# axiom_beta_sensor_cmv12000_tht_v0_16_r1_.net
KiCad netlist of a schematic drawn in EAGLE
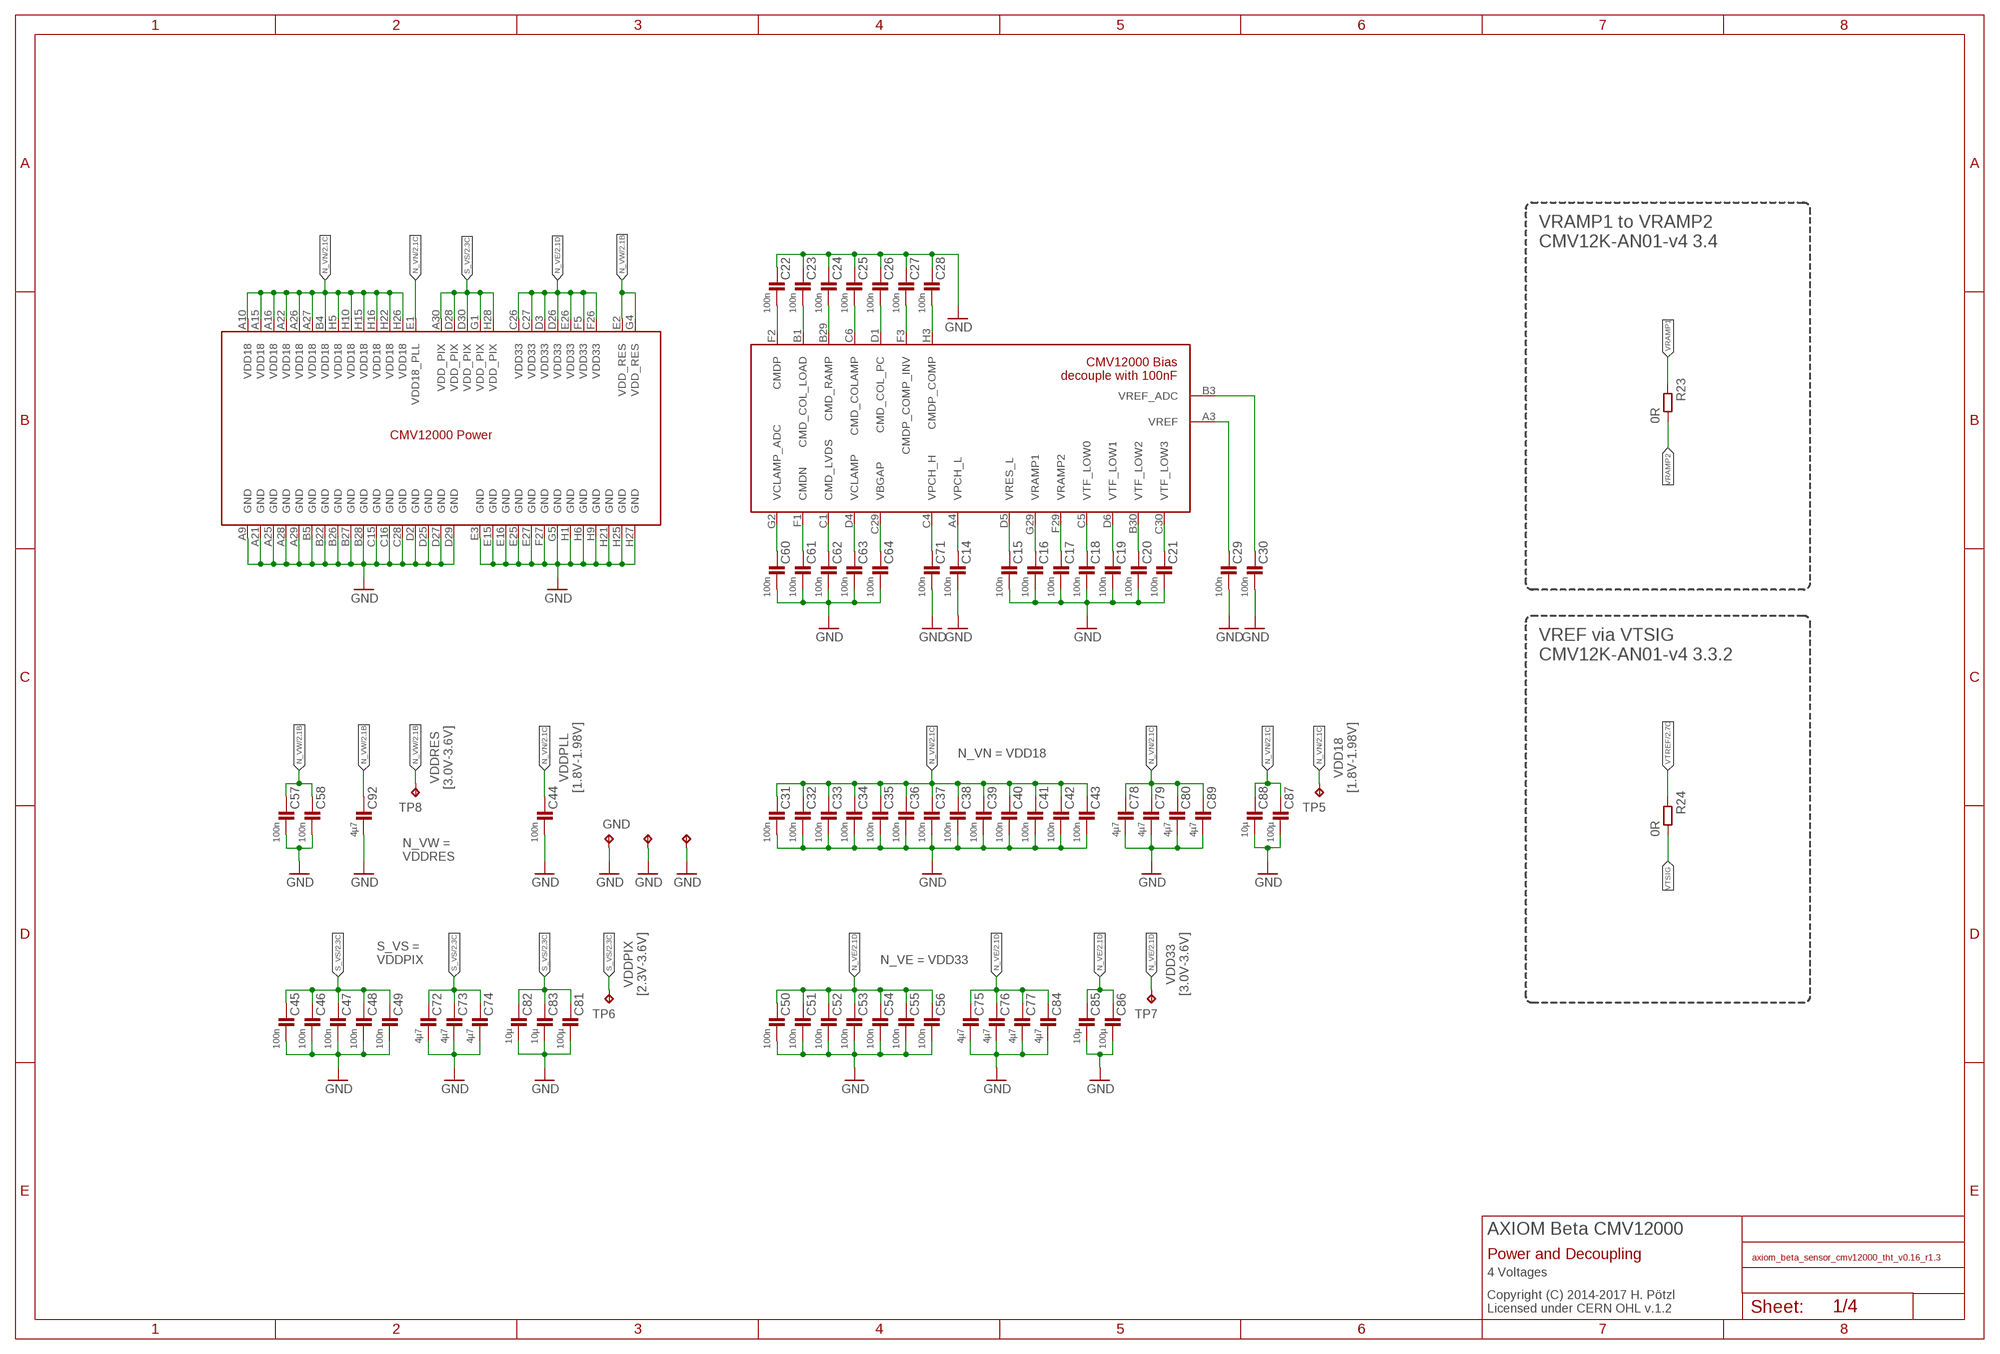
[diagram p0: schematic, sheet 1]
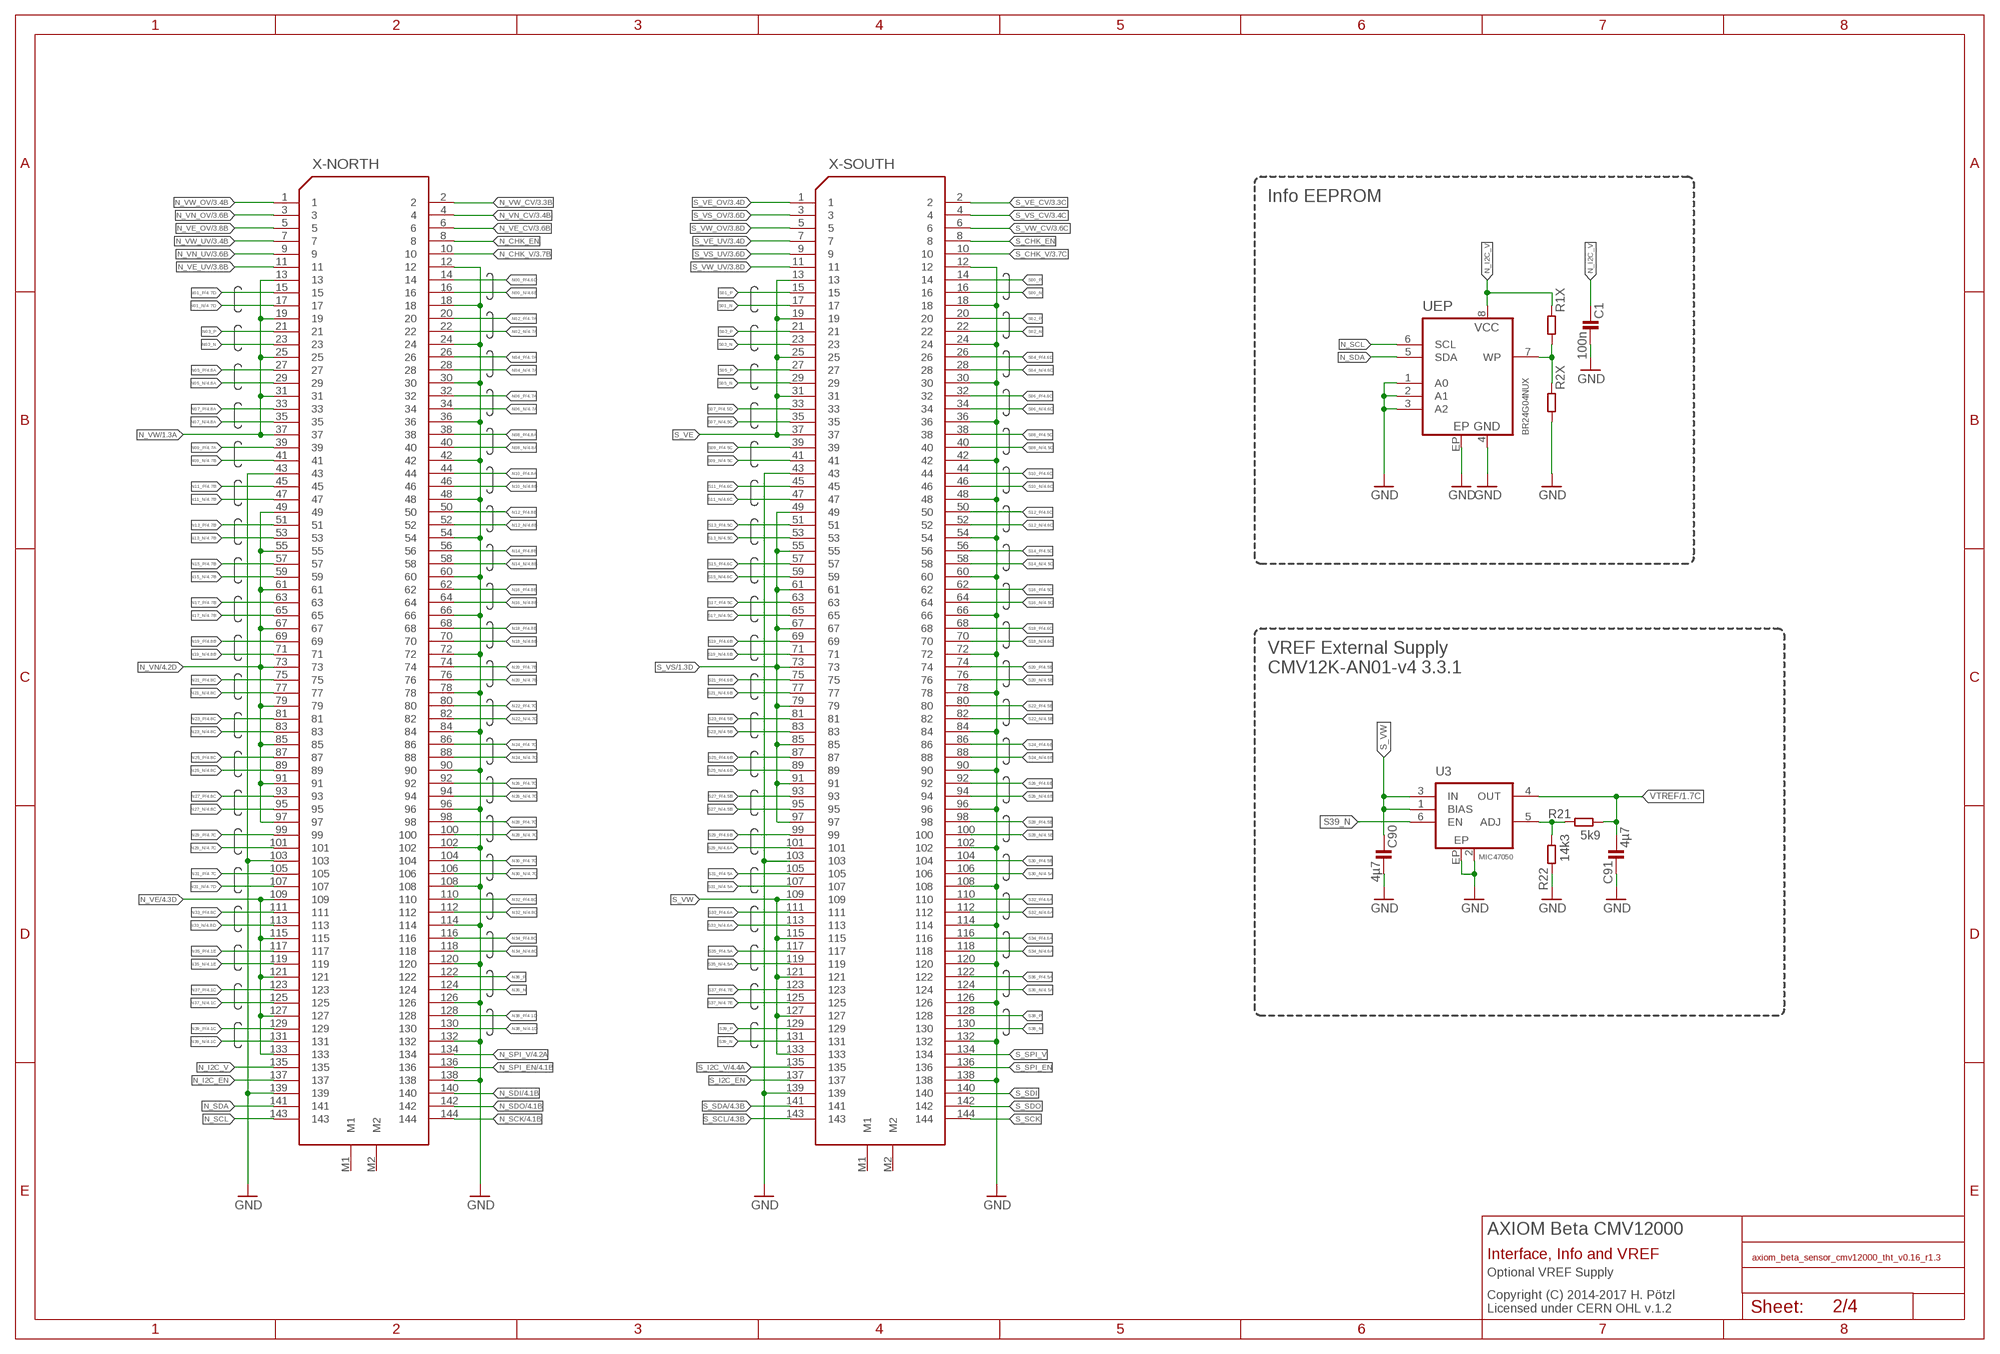
[diagram p1: schematic, sheet 2]
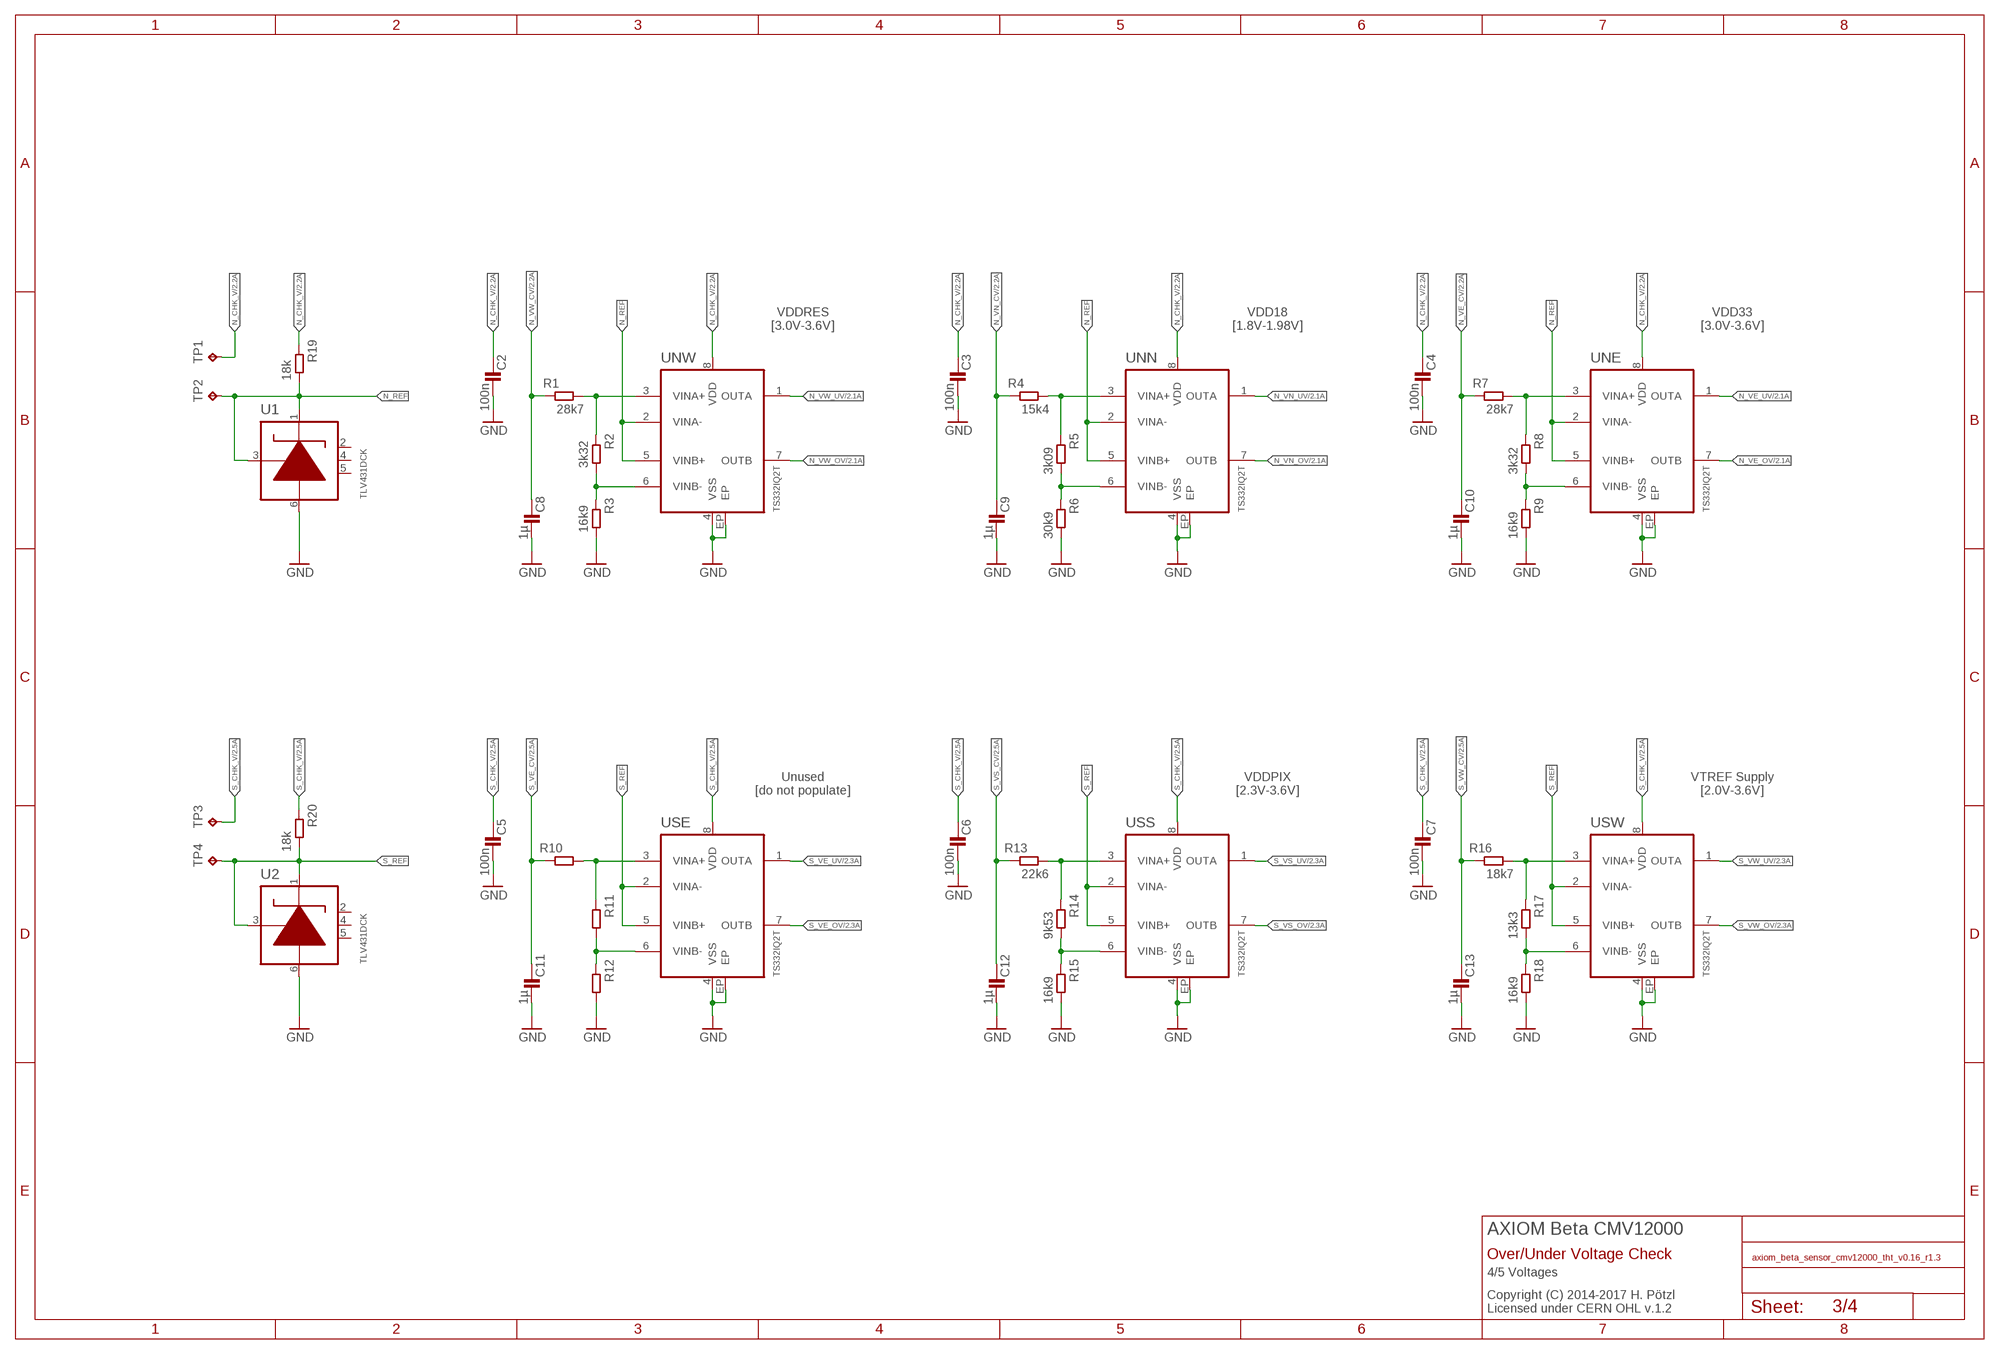
[diagram p2: schematic, sheet 3]
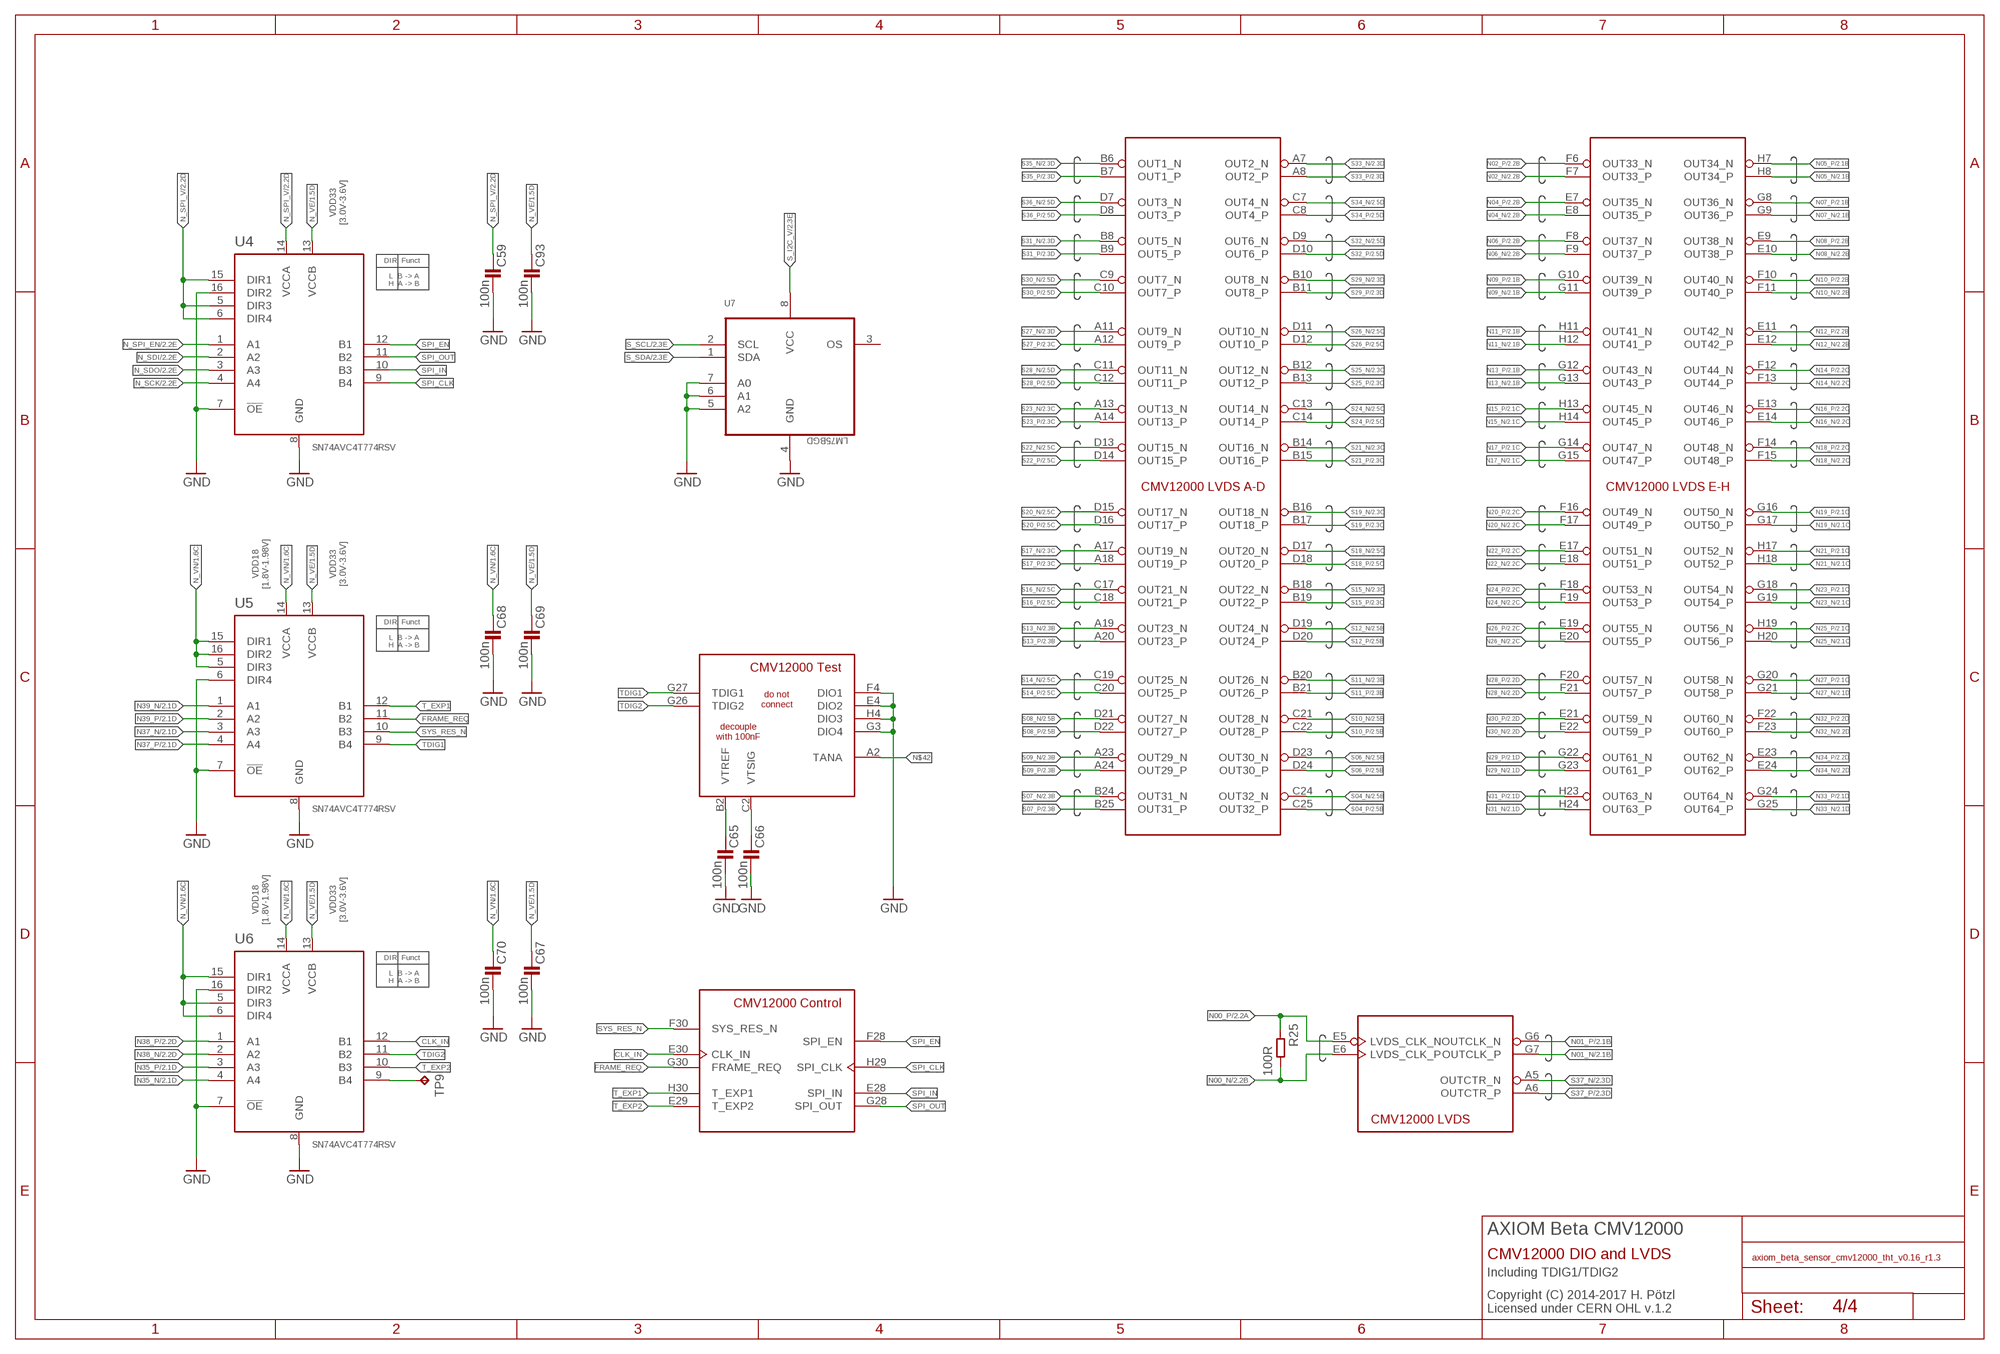
[diagram p3: schematic, sheet 4]

(export (version "E")
  (design (tool "Eeschema 10.0.6"))
  (components
    (comp (ref "C1")
      (value "100n")
      (footprint "eagle-import:0402-C")
      (libsource (lib "eagle-import") (part "C0402-C"))
    )
    (comp (ref "C90")
      (value "4µ7")
      (footprint "eagle-import:0402-C")
      (libsource (lib "eagle-import") (part "C0402-C"))
    )
    (comp (ref "C91")
      (value "4µ7")
      (footprint "eagle-import:0402-C")
      (libsource (lib "eagle-import") (part "C0402-C"))
    )
    (comp (ref "R1X")
      (value "R0402-C")
      (footprint "eagle-import:0402-C")
      (libsource (lib "eagle-import") (part "R0402-C"))
    )
    (comp (ref "R2X")
      (value "R0402-C")
      (footprint "eagle-import:0402-C")
      (libsource (lib "eagle-import") (part "R0402-C"))
    )
    (comp (ref "R21")
      (value "5k9")
      (footprint "eagle-import:0402-C")
      (libsource (lib "eagle-import") (part "R0402-C"))
    )
    (comp (ref "R22")
      (value "14k3")
      (footprint "eagle-import:0402-C")
      (libsource (lib "eagle-import") (part "R0402-C"))
    )
    (comp (ref "U3")
      (value "MIC47050")
      (footprint "eagle-import:MLF-6")
      (libsource (lib "eagle-import") (part "MIC47050-ADJ"))
    )
    (comp (ref "UEP")
      (value "BR24G04NUX")
      (footprint "eagle-import:DFN200X300X100-9N")
      (libsource (lib "eagle-import") (part "BR24G04NUX"))
    )
    (comp (ref "X-NORTH")
      (value "FX10-144P")
      (footprint "eagle-import:FX10A-144P")
      (libsource (lib "eagle-import") (part "FX10-144P"))
    )
    (comp (ref "X-SOUTH")
      (value "FX10-144P")
      (footprint "eagle-import:FX10A-144P")
      (libsource (lib "eagle-import") (part "FX10-144P"))
    )
    (comp (ref "C2")
      (value "100n")
      (footprint "eagle-import:0402-C")
      (libsource (lib "eagle-import") (part "C0402-C"))
    )
    (comp (ref "C3")
      (value "100n")
      (footprint "eagle-import:0402-C")
      (libsource (lib "eagle-import") (part "C0402-C"))
    )
    (comp (ref "C4")
      (value "100n")
      (footprint "eagle-import:0402-C")
      (libsource (lib "eagle-import") (part "C0402-C"))
    )
    (comp (ref "C5")
      (value "100n")
      (footprint "eagle-import:0402-C")
      (libsource (lib "eagle-import") (part "C0402-C"))
    )
    (comp (ref "C6")
      (value "100n")
      (footprint "eagle-import:0402-C")
      (libsource (lib "eagle-import") (part "C0402-C"))
    )
    (comp (ref "C7")
      (value "100n")
      (footprint "eagle-import:0402-C")
      (libsource (lib "eagle-import") (part "C0402-C"))
    )
    (comp (ref "C8")
      (value "1µ")
      (footprint "eagle-import:0402-C")
      (libsource (lib "eagle-import") (part "C0402-C"))
    )
    (comp (ref "C9")
      (value "1µ")
      (footprint "eagle-import:0402-C")
      (libsource (lib "eagle-import") (part "C0402-C"))
    )
    (comp (ref "C10")
      (value "1µ")
      (footprint "eagle-import:0402-C")
      (libsource (lib "eagle-import") (part "C0402-C"))
    )
    (comp (ref "C11")
      (value "1µ")
      (footprint "eagle-import:0402-C")
      (libsource (lib "eagle-import") (part "C0402-C"))
    )
    (comp (ref "C12")
      (value "1µ")
      (footprint "eagle-import:0402-C")
      (libsource (lib "eagle-import") (part "C0402-C"))
    )
    (comp (ref "C13")
      (value "1µ")
      (footprint "eagle-import:0402-C")
      (libsource (lib "eagle-import") (part "C0402-C"))
    )
    (comp (ref "R1")
      (value "28k7")
      (footprint "eagle-import:0402-C")
      (libsource (lib "eagle-import") (part "R0402-C"))
    )
    (comp (ref "R2")
      (value "3k32")
      (footprint "eagle-import:0402-C")
      (libsource (lib "eagle-import") (part "R0402-C"))
    )
    (comp (ref "R3")
      (value "16k9")
      (footprint "eagle-import:0402-C")
      (libsource (lib "eagle-import") (part "R0402-C"))
    )
    (comp (ref "R4")
      (value "15k4")
      (footprint "eagle-import:0402-C")
      (libsource (lib "eagle-import") (part "R0402-C"))
    )
    (comp (ref "R5")
      (value "3k09")
      (footprint "eagle-import:0402-C")
      (libsource (lib "eagle-import") (part "R0402-C"))
    )
    (comp (ref "R6")
      (value "30k9")
      (footprint "eagle-import:0402-C")
      (libsource (lib "eagle-import") (part "R0402-C"))
    )
    (comp (ref "R7")
      (value "28k7")
      (footprint "eagle-import:0402-C")
      (libsource (lib "eagle-import") (part "R0402-C"))
    )
    (comp (ref "R8")
      (value "3k32")
      (footprint "eagle-import:0402-C")
      (libsource (lib "eagle-import") (part "R0402-C"))
    )
    (comp (ref "R9")
      (value "16k9")
      (footprint "eagle-import:0402-C")
      (libsource (lib "eagle-import") (part "R0402-C"))
    )
    (comp (ref "R10")
      (value "R0402-C")
      (footprint "eagle-import:0402-C")
      (libsource (lib "eagle-import") (part "R0402-C"))
    )
    (comp (ref "R11")
      (value "R0402-C")
      (footprint "eagle-import:0402-C")
      (libsource (lib "eagle-import") (part "R0402-C"))
    )
    (comp (ref "R12")
      (value "R0402-C")
      (footprint "eagle-import:0402-C")
      (libsource (lib "eagle-import") (part "R0402-C"))
    )
    (comp (ref "R13")
      (value "22k6")
      (footprint "eagle-import:0402-C")
      (libsource (lib "eagle-import") (part "R0402-C"))
    )
    (comp (ref "R14")
      (value "9k53")
      (footprint "eagle-import:0402-C")
      (libsource (lib "eagle-import") (part "R0402-C"))
    )
    (comp (ref "R15")
      (value "16k9")
      (footprint "eagle-import:0402-C")
      (libsource (lib "eagle-import") (part "R0402-C"))
    )
    (comp (ref "R16")
      (value "18k7")
      (footprint "eagle-import:0402-C")
      (libsource (lib "eagle-import") (part "R0402-C"))
    )
    (comp (ref "R17")
      (value "13k3")
      (footprint "eagle-import:0402-C")
      (libsource (lib "eagle-import") (part "R0402-C"))
    )
    (comp (ref "R18")
      (value "16k9")
      (footprint "eagle-import:0402-C")
      (libsource (lib "eagle-import") (part "R0402-C"))
    )
    (comp (ref "R19")
      (value "18k")
      (footprint "eagle-import:0402-C")
      (libsource (lib "eagle-import") (part "R0402-C"))
    )
    (comp (ref "R20")
      (value "18k")
      (footprint "eagle-import:0402-C")
      (libsource (lib "eagle-import") (part "R0402-C"))
    )
    (comp (ref "TP1")
      (value "TPTP10R")
      (footprint "eagle-import:TP10R")
      (libsource (lib "eagle-import") (part "TPTP10R"))
    )
    (comp (ref "TP2")
      (value "TPTP10R")
      (footprint "eagle-import:TP10R")
      (libsource (lib "eagle-import") (part "TPTP10R"))
    )
    (comp (ref "TP3")
      (value "TPTP10R")
      (footprint "eagle-import:TP10R")
      (libsource (lib "eagle-import") (part "TPTP10R"))
    )
    (comp (ref "TP4")
      (value "TPTP10R")
      (footprint "eagle-import:TP10R")
      (libsource (lib "eagle-import") (part "TPTP10R"))
    )
    (comp (ref "U1")
      (value "TLV431DCK")
      (footprint "eagle-import:SOT65P210X110-6N")
      (libsource (lib "eagle-import") (part "TLV431DCK"))
    )
    (comp (ref "U2")
      (value "TLV431DCK")
      (footprint "eagle-import:SOT65P210X110-6N")
      (libsource (lib "eagle-import") (part "TLV431DCK"))
    )
    (comp (ref "UNE")
      (value "TS332IQ2T")
      (footprint "eagle-import:DFN200X200X100-9N")
      (libsource (lib "eagle-import") (part "TS332IQ2T"))
    )
    (comp (ref "UNN")
      (value "TS332IQ2T")
      (footprint "eagle-import:DFN200X200X100-9N")
      (libsource (lib "eagle-import") (part "TS332IQ2T"))
    )
    (comp (ref "UNW")
      (value "TS332IQ2T")
      (footprint "eagle-import:DFN200X200X100-9N")
      (libsource (lib "eagle-import") (part "TS332IQ2T"))
    )
    (comp (ref "USE")
      (value "TS332IQ2T")
      (footprint "eagle-import:DFN200X200X100-9N")
      (libsource (lib "eagle-import") (part "TS332IQ2T"))
    )
    (comp (ref "USS")
      (value "TS332IQ2T")
      (footprint "eagle-import:DFN200X200X100-9N")
      (libsource (lib "eagle-import") (part "TS332IQ2T"))
    )
    (comp (ref "USW")
      (value "TS332IQ2T")
      (footprint "eagle-import:DFN200X200X100-9N")
      (libsource (lib "eagle-import") (part "TS332IQ2T"))
    )
    (comp (ref "C59")
      (value "100n")
      (footprint "eagle-import:0402-C")
      (libsource (lib "eagle-import") (part "C0402-C"))
    )
    (comp (ref "C65")
      (value "100n")
      (footprint "eagle-import:0402-C")
      (libsource (lib "eagle-import") (part "C0402-C"))
    )
    (comp (ref "C66")
      (value "100n")
      (footprint "eagle-import:0402-C")
      (libsource (lib "eagle-import") (part "C0402-C"))
    )
    (comp (ref "C67")
      (value "100n")
      (footprint "eagle-import:0402-C")
      (libsource (lib "eagle-import") (part "C0402-C"))
    )
    (comp (ref "C68")
      (value "100n")
      (footprint "eagle-import:0402-C")
      (libsource (lib "eagle-import") (part "C0402-C"))
    )
    (comp (ref "C69")
      (value "100n")
      (footprint "eagle-import:0402-C")
      (libsource (lib "eagle-import") (part "C0402-C"))
    )
    (comp (ref "C70")
      (value "100n")
      (footprint "eagle-import:0402-C")
      (libsource (lib "eagle-import") (part "C0402-C"))
    )
    (comp (ref "C93")
      (value "100n")
      (footprint "eagle-import:0402-C")
      (libsource (lib "eagle-import") (part "C0402-C"))
    )
    (comp (ref "R25")
      (value "100R")
      (footprint "eagle-import:0402-C")
      (libsource (lib "eagle-import") (part "R0402-C"))
    )
    (comp (ref "SENSOR")
      (value "CMV12000ANDON")
      (footprint "eagle-import:10-30-07-237-400T4")
      (libsource (lib "eagle-import") (part "CMV12000ANDON"))
    )
    (comp (ref "TP9")
      (value "TPTP10R")
      (footprint "eagle-import:TP10R")
      (libsource (lib "eagle-import") (part "TPTP10R"))
    )
    (comp (ref "U4")
      (value "SN74AVC4T774RSV")
      (footprint "eagle-import:QFN40P185X265X55-16N")
      (libsource (lib "eagle-import") (part "SN74AVC4T774RSV"))
    )
    (comp (ref "U5")
      (value "SN74AVC4T774RSV")
      (footprint "eagle-import:QFN40P185X265X55-16N")
      (libsource (lib "eagle-import") (part "SN74AVC4T774RSV"))
    )
    (comp (ref "U6")
      (value "SN74AVC4T774RSV")
      (footprint "eagle-import:QFN40P185X265X55-16N")
      (libsource (lib "eagle-import") (part "SN74AVC4T774RSV"))
    )
    (comp (ref "U7")
      (value "LM75BGD")
      (footprint "eagle-import:SOT996-2_3")
      (libsource (lib "eagle-import") (part "LM75BGD"))
    )
    (comp (ref "C14")
      (value "100n")
      (footprint "eagle-import:0402-C")
      (libsource (lib "eagle-import") (part "C0402-C"))
    )
    (comp (ref "C15")
      (value "100n")
      (footprint "eagle-import:0402-C")
      (libsource (lib "eagle-import") (part "C0402-C"))
    )
    (comp (ref "C16")
      (value "100n")
      (footprint "eagle-import:0402-C")
      (libsource (lib "eagle-import") (part "C0402-C"))
    )
    (comp (ref "C17")
      (value "100n")
      (footprint "eagle-import:0402-C")
      (libsource (lib "eagle-import") (part "C0402-C"))
    )
    (comp (ref "C18")
      (value "100n")
      (footprint "eagle-import:0402-C")
      (libsource (lib "eagle-import") (part "C0402-C"))
    )
    (comp (ref "C19")
      (value "100n")
      (footprint "eagle-import:0402-C")
      (libsource (lib "eagle-import") (part "C0402-C"))
    )
    (comp (ref "C20")
      (value "100n")
      (footprint "eagle-import:0402-C")
      (libsource (lib "eagle-import") (part "C0402-C"))
    )
    (comp (ref "C21")
      (value "100n")
      (footprint "eagle-import:0402-C")
      (libsource (lib "eagle-import") (part "C0402-C"))
    )
    (comp (ref "C22")
      (value "100n")
      (footprint "eagle-import:0402-C")
      (libsource (lib "eagle-import") (part "C0402-C"))
    )
    (comp (ref "C23")
      (value "100n")
      (footprint "eagle-import:0402-C")
      (libsource (lib "eagle-import") (part "C0402-C"))
    )
    (comp (ref "C24")
      (value "100n")
      (footprint "eagle-import:0402-C")
      (libsource (lib "eagle-import") (part "C0402-C"))
    )
    (comp (ref "C25")
      (value "100n")
      (footprint "eagle-import:0402-C")
      (libsource (lib "eagle-import") (part "C0402-C"))
    )
    (comp (ref "C26")
      (value "100n")
      (footprint "eagle-import:0402-C")
      (libsource (lib "eagle-import") (part "C0402-C"))
    )
    (comp (ref "C27")
      (value "100n")
      (footprint "eagle-import:0402-C")
      (libsource (lib "eagle-import") (part "C0402-C"))
    )
    (comp (ref "C28")
      (value "100n")
      (footprint "eagle-import:0402-C")
      (libsource (lib "eagle-import") (part "C0402-C"))
    )
    (comp (ref "C29")
      (value "100n")
      (footprint "eagle-import:0402-C")
      (libsource (lib "eagle-import") (part "C0402-C"))
    )
    (comp (ref "C30")
      (value "100n")
      (footprint "eagle-import:0402-C")
      (libsource (lib "eagle-import") (part "C0402-C"))
    )
    (comp (ref "C31")
      (value "100n")
      (footprint "eagle-import:0402-C")
      (libsource (lib "eagle-import") (part "C0402-C"))
    )
    (comp (ref "C32")
      (value "100n")
      (footprint "eagle-import:0402-C")
      (libsource (lib "eagle-import") (part "C0402-C"))
    )
    (comp (ref "C33")
      (value "100n")
      (footprint "eagle-import:0402-C")
      (libsource (lib "eagle-import") (part "C0402-C"))
    )
    (comp (ref "C34")
      (value "100n")
      (footprint "eagle-import:0402-C")
      (libsource (lib "eagle-import") (part "C0402-C"))
    )
    (comp (ref "C35")
      (value "100n")
      (footprint "eagle-import:0402-C")
      (libsource (lib "eagle-import") (part "C0402-C"))
    )
    (comp (ref "C36")
      (value "100n")
      (footprint "eagle-import:0402-C")
      (libsource (lib "eagle-import") (part "C0402-C"))
    )
    (comp (ref "C37")
      (value "100n")
      (footprint "eagle-import:0402-C")
      (libsource (lib "eagle-import") (part "C0402-C"))
    )
    (comp (ref "C38")
      (value "100n")
      (footprint "eagle-import:0402-C")
      (libsource (lib "eagle-import") (part "C0402-C"))
    )
    (comp (ref "C39")
      (value "100n")
      (footprint "eagle-import:0402-C")
      (libsource (lib "eagle-import") (part "C0402-C"))
    )
    (comp (ref "C40")
      (value "100n")
      (footprint "eagle-import:0402-C")
      (libsource (lib "eagle-import") (part "C0402-C"))
    )
    (comp (ref "C41")
      (value "100n")
      (footprint "eagle-import:0402-C")
      (libsource (lib "eagle-import") (part "C0402-C"))
    )
    (comp (ref "C42")
      (value "100n")
      (footprint "eagle-import:0402-C")
      (libsource (lib "eagle-import") (part "C0402-C"))
    )
    (comp (ref "C43")
      (value "100n")
      (footprint "eagle-import:0402-C")
      (libsource (lib "eagle-import") (part "C0402-C"))
    )
    (comp (ref "C44")
      (value "100n")
      (footprint "eagle-import:0402-C")
      (libsource (lib "eagle-import") (part "C0402-C"))
    )
    (comp (ref "C45")
      (value "100n")
      (footprint "eagle-import:0402-C")
      (libsource (lib "eagle-import") (part "C0402-C"))
    )
    (comp (ref "C46")
      (value "100n")
      (footprint "eagle-import:0402-C")
      (libsource (lib "eagle-import") (part "C0402-C"))
    )
    (comp (ref "C47")
      (value "100n")
      (footprint "eagle-import:0402-C")
      (libsource (lib "eagle-import") (part "C0402-C"))
    )
    (comp (ref "C48")
      (value "100n")
      (footprint "eagle-import:0402-C")
      (libsource (lib "eagle-import") (part "C0402-C"))
    )
    (comp (ref "C49")
      (value "100n")
      (footprint "eagle-import:0402-C")
      (libsource (lib "eagle-import") (part "C0402-C"))
    )
    (comp (ref "C50")
      (value "100n")
      (footprint "eagle-import:0402-C")
      (libsource (lib "eagle-import") (part "C0402-C"))
    )
    (comp (ref "C51")
      (value "100n")
      (footprint "eagle-import:0402-C")
      (libsource (lib "eagle-import") (part "C0402-C"))
    )
    (comp (ref "C52")
      (value "100n")
      (footprint "eagle-import:0402-C")
      (libsource (lib "eagle-import") (part "C0402-C"))
    )
    (comp (ref "C53")
      (value "100n")
      (footprint "eagle-import:0402-C")
      (libsource (lib "eagle-import") (part "C0402-C"))
    )
    (comp (ref "C54")
      (value "100n")
      (footprint "eagle-import:0402-C")
      (libsource (lib "eagle-import") (part "C0402-C"))
    )
    (comp (ref "C55")
      (value "100n")
      (footprint "eagle-import:0402-C")
      (libsource (lib "eagle-import") (part "C0402-C"))
    )
    (comp (ref "C56")
      (value "100n")
      (footprint "eagle-import:0402-C")
      (libsource (lib "eagle-import") (part "C0402-C"))
    )
    (comp (ref "C57")
      (value "100n")
      (footprint "eagle-import:0402-C")
      (libsource (lib "eagle-import") (part "C0402-C"))
    )
    (comp (ref "C58")
      (value "100n")
      (footprint "eagle-import:0402-C")
      (libsource (lib "eagle-import") (part "C0402-C"))
    )
    (comp (ref "C60")
      (value "100n")
      (footprint "eagle-import:0402-C")
      (libsource (lib "eagle-import") (part "C0402-C"))
    )
    (comp (ref "C61")
      (value "100n")
      (footprint "eagle-import:0402-C")
      (libsource (lib "eagle-import") (part "C0402-C"))
    )
    (comp (ref "C62")
      (value "100n")
      (footprint "eagle-import:0402-C")
      (libsource (lib "eagle-import") (part "C0402-C"))
    )
    (comp (ref "C63")
      (value "100n")
      (footprint "eagle-import:0402-C")
      (libsource (lib "eagle-import") (part "C0402-C"))
    )
    (comp (ref "C64")
      (value "100n")
      (footprint "eagle-import:0402-C")
      (libsource (lib "eagle-import") (part "C0402-C"))
    )
    (comp (ref "C71")
      (value "100n")
      (footprint "eagle-import:0402-C")
      (libsource (lib "eagle-import") (part "C0402-C"))
    )
    (comp (ref "C72")
      (value "4µ7")
      (footprint "eagle-import:0402-B")
      (libsource (lib "eagle-import") (part "C0402-B"))
    )
    (comp (ref "C73")
      (value "4µ7")
      (footprint "eagle-import:0402-C")
      (libsource (lib "eagle-import") (part "C0402-C"))
    )
    (comp (ref "C74")
      (value "4µ7")
      (footprint "eagle-import:0402-C")
      (libsource (lib "eagle-import") (part "C0402-C"))
    )
    (comp (ref "C75")
      (value "4µ7")
      (footprint "eagle-import:0402-C")
      (libsource (lib "eagle-import") (part "C0402-C"))
    )
    (comp (ref "C76")
      (value "4µ7")
      (footprint "eagle-import:0402-C")
      (libsource (lib "eagle-import") (part "C0402-C"))
    )
    (comp (ref "C77")
      (value "4µ7")
      (footprint "eagle-import:0402-B")
      (libsource (lib "eagle-import") (part "C0402-B"))
    )
    (comp (ref "C78")
      (value "4µ7")
      (footprint "eagle-import:0402-B")
      (libsource (lib "eagle-import") (part "C0402-B"))
    )
    (comp (ref "C79")
      (value "4µ7")
      (footprint "eagle-import:0402-C")
      (libsource (lib "eagle-import") (part "C0402-C"))
    )
    (comp (ref "C80")
      (value "4µ7")
      (footprint "eagle-import:0402-C")
      (libsource (lib "eagle-import") (part "C0402-C"))
    )
    (comp (ref "C81")
      (value "100µ")
      (footprint "eagle-import:1206-B")
      (libsource (lib "eagle-import") (part "C1206-B"))
    )
    (comp (ref "C82")
      (value "10µ")
      (footprint "eagle-import:0603-C")
      (libsource (lib "eagle-import") (part "C0603-C"))
    )
    (comp (ref "C83")
      (value "10µ")
      (footprint "eagle-import:0603-C")
      (libsource (lib "eagle-import") (part "C0603-C"))
    )
    (comp (ref "C84")
      (value "4µ7")
      (footprint "eagle-import:0402-C")
      (libsource (lib "eagle-import") (part "C0402-C"))
    )
    (comp (ref "C85")
      (value "10µ")
      (footprint "eagle-import:0603-C")
      (libsource (lib "eagle-import") (part "C0603-C"))
    )
    (comp (ref "C86")
      (value "100µ")
      (footprint "eagle-import:1206-B")
      (libsource (lib "eagle-import") (part "C1206-B"))
    )
    (comp (ref "C87")
      (value "100µ")
      (footprint "eagle-import:1206-B")
      (libsource (lib "eagle-import") (part "C1206-B"))
    )
    (comp (ref "C88")
      (value "10µ")
      (footprint "eagle-import:0603-C")
      (libsource (lib "eagle-import") (part "C0603-C"))
    )
    (comp (ref "C89")
      (value "4µ7")
      (footprint "eagle-import:0402-C")
      (libsource (lib "eagle-import") (part "C0402-C"))
    )
    (comp (ref "C92")
      (value "4µ7")
      (footprint "eagle-import:0402-C")
      (libsource (lib "eagle-import") (part "C0402-C"))
    )
    (comp (ref "GND")
      (value "TPTP10R")
      (footprint "eagle-import:TP10R")
      (libsource (lib "eagle-import") (part "TPTP10R"))
    )
    (comp (ref "GND75")
      (value "TPTP10R")
      (footprint "eagle-import:TP10R")
      (libsource (lib "eagle-import") (part "TPTP10R"))
    )
    (comp (ref "GND77")
      (value "TPTP10R")
      (footprint "eagle-import:TP10R")
      (libsource (lib "eagle-import") (part "TPTP10R"))
    )
    (comp (ref "R23")
      (value "0R")
      (footprint "eagle-import:0402-C")
      (libsource (lib "eagle-import") (part "R0402-C"))
    )
    (comp (ref "R24")
      (value "0R")
      (footprint "eagle-import:0402-C")
      (libsource (lib "eagle-import") (part "R0402-C"))
    )
    (comp (ref "TP5")
      (value "TPTP10R")
      (footprint "eagle-import:TP10R")
      (libsource (lib "eagle-import") (part "TPTP10R"))
    )
    (comp (ref "TP6")
      (value "TPTP10R")
      (footprint "eagle-import:TP10R")
      (libsource (lib "eagle-import") (part "TPTP10R"))
    )
    (comp (ref "TP7")
      (value "TPTP10R")
      (footprint "eagle-import:TP10R")
      (libsource (lib "eagle-import") (part "TPTP10R"))
    )
    (comp (ref "TP8")
      (value "TPTP10R")
      (footprint "eagle-import:TP10R")
      (libsource (lib "eagle-import") (part "TPTP10R"))
    )
  )
  (nets
    (net (code "1") (name "CLK_IN") (class "Default")
      (node (ref "SENSOR") (pin "E30") (pinfunction "CLK_IN_E30") (pintype "input"))
      (node (ref "U6") (pin "12") (pinfunction "B1_12") (pintype "bidirectional"))
    )
    (net (code "2") (name "FRAME_REQ") (class "Default")
      (node (ref "SENSOR") (pin "G30") (pinfunction "FRAME_REQ_G30") (pintype "input"))
      (node (ref "U5") (pin "11") (pinfunction "B2_11") (pintype "bidirectional"))
    )
    (net (code "3") (name "GND") (class "Default")
      (node (ref "C1") (pin "2") (pinfunction "2_2") (pintype "passive"))
      (node (ref "C10") (pin "2") (pinfunction "2_2") (pintype "passive"))
      (node (ref "C11") (pin "2") (pinfunction "2_2") (pintype "passive"))
      (node (ref "C12") (pin "2") (pinfunction "2_2") (pintype "passive"))
      (node (ref "C13") (pin "2") (pinfunction "2_2") (pintype "passive"))
      (node (ref "C14") (pin "2") (pinfunction "2_2") (pintype "passive"))
      (node (ref "C15") (pin "2") (pinfunction "2_2") (pintype "passive"))
      (node (ref "C16") (pin "2") (pinfunction "2_2") (pintype "passive"))
      (node (ref "C17") (pin "2") (pinfunction "2_2") (pintype "passive"))
      (node (ref "C18") (pin "2") (pinfunction "2_2") (pintype "passive"))
      (node (ref "C19") (pin "2") (pinfunction "2_2") (pintype "passive"))
      (node (ref "C2") (pin "2") (pinfunction "2_2") (pintype "passive"))
      (node (ref "C20") (pin "2") (pinfunction "2_2") (pintype "passive"))
      (node (ref "C21") (pin "2") (pinfunction "2_2") (pintype "passive"))
      (node (ref "C22") (pin "1") (pinfunction "1_1") (pintype "passive"))
      (node (ref "C23") (pin "1") (pinfunction "1_1") (pintype "passive"))
      (node (ref "C24") (pin "1") (pinfunction "1_1") (pintype "passive"))
      (node (ref "C25") (pin "1") (pinfunction "1_1") (pintype "passive"))
      (node (ref "C26") (pin "1") (pinfunction "1_1") (pintype "passive"))
      (node (ref "C27") (pin "1") (pinfunction "1_1") (pintype "passive"))
      (node (ref "C28") (pin "1") (pinfunction "1_1") (pintype "passive"))
      (node (ref "C29") (pin "2") (pinfunction "2_2") (pintype "passive"))
      (node (ref "C3") (pin "2") (pinfunction "2_2") (pintype "passive"))
      (node (ref "C30") (pin "2") (pinfunction "2_2") (pintype "passive"))
      (node (ref "C31") (pin "2") (pinfunction "2_2") (pintype "passive"))
      (node (ref "C32") (pin "2") (pinfunction "2_2") (pintype "passive"))
      (node (ref "C33") (pin "2") (pinfunction "2_2") (pintype "passive"))
      (node (ref "C34") (pin "2") (pinfunction "2_2") (pintype "passive"))
      (node (ref "C35") (pin "2") (pinfunction "2_2") (pintype "passive"))
      (node (ref "C36") (pin "2") (pinfunction "2_2") (pintype "passive"))
      (node (ref "C37") (pin "2") (pinfunction "2_2") (pintype "passive"))
      (node (ref "C38") (pin "2") (pinfunction "2_2") (pintype "passive"))
      (node (ref "C39") (pin "2") (pinfunction "2_2") (pintype "passive"))
      (node (ref "C4") (pin "2") (pinfunction "2_2") (pintype "passive"))
      (node (ref "C40") (pin "2") (pinfunction "2_2") (pintype "passive"))
      (node (ref "C41") (pin "2") (pinfunction "2_2") (pintype "passive"))
      (node (ref "C42") (pin "2") (pinfunction "2_2") (pintype "passive"))
      (node (ref "C43") (pin "2") (pinfunction "2_2") (pintype "passive"))
      (node (ref "C44") (pin "2") (pinfunction "2_2") (pintype "passive"))
      (node (ref "C45") (pin "2") (pinfunction "2_2") (pintype "passive"))
      (node (ref "C46") (pin "2") (pinfunction "2_2") (pintype "passive"))
      (node (ref "C47") (pin "2") (pinfunction "2_2") (pintype "passive"))
      (node (ref "C48") (pin "2") (pinfunction "2_2") (pintype "passive"))
      (node (ref "C49") (pin "2") (pinfunction "2_2") (pintype "passive"))
      (node (ref "C5") (pin "2") (pinfunction "2_2") (pintype "passive"))
      (node (ref "C50") (pin "2") (pinfunction "2_2") (pintype "passive"))
      (node (ref "C51") (pin "2") (pinfunction "2_2") (pintype "passive"))
      (node (ref "C52") (pin "2") (pinfunction "2_2") (pintype "passive"))
      (node (ref "C53") (pin "2") (pinfunction "2_2") (pintype "passive"))
      (node (ref "C54") (pin "2") (pinfunction "2_2") (pintype "passive"))
      (node (ref "C55") (pin "2") (pinfunction "2_2") (pintype "passive"))
      (node (ref "C56") (pin "2") (pinfunction "2_2") (pintype "passive"))
      (node (ref "C57") (pin "2") (pinfunction "2_2") (pintype "passive"))
      (node (ref "C58") (pin "2") (pinfunction "2_2") (pintype "passive"))
      (node (ref "C59") (pin "2") (pinfunction "2_2") (pintype "passive"))
      (node (ref "C6") (pin "2") (pinfunction "2_2") (pintype "passive"))
      (node (ref "C60") (pin "2") (pinfunction "2_2") (pintype "passive"))
      (node (ref "C61") (pin "2") (pinfunction "2_2") (pintype "passive"))
      (node (ref "C62") (pin "2") (pinfunction "2_2") (pintype "passive"))
      (node (ref "C63") (pin "2") (pinfunction "2_2") (pintype "passive"))
      (node (ref "C64") (pin "2") (pinfunction "2_2") (pintype "passive"))
      (node (ref "C65") (pin "2") (pinfunction "2_2") (pintype "passive"))
      (node (ref "C66") (pin "2") (pinfunction "2_2") (pintype "passive"))
      (node (ref "C67") (pin "2") (pinfunction "2_2") (pintype "passive"))
      (node (ref "C68") (pin "2") (pinfunction "2_2") (pintype "passive"))
      (node (ref "C69") (pin "2") (pinfunction "2_2") (pintype "passive"))
      (node (ref "C7") (pin "2") (pinfunction "2_2") (pintype "passive"))
      (node (ref "C70") (pin "2") (pinfunction "2_2") (pintype "passive"))
      (node (ref "C71") (pin "2") (pinfunction "2_2") (pintype "passive"))
      (node (ref "C72") (pin "2") (pinfunction "2_2") (pintype "passive"))
      (node (ref "C73") (pin "2") (pinfunction "2_2") (pintype "passive"))
      (node (ref "C74") (pin "2") (pinfunction "2_2") (pintype "passive"))
      (node (ref "C75") (pin "2") (pinfunction "2_2") (pintype "passive"))
      (node (ref "C76") (pin "2") (pinfunction "2_2") (pintype "passive"))
      (node (ref "C77") (pin "2") (pinfunction "2_2") (pintype "passive"))
      (node (ref "C78") (pin "2") (pinfunction "2_2") (pintype "passive"))
      (node (ref "C79") (pin "2") (pinfunction "2_2") (pintype "passive"))
      (node (ref "C8") (pin "2") (pinfunction "2_2") (pintype "passive"))
      (node (ref "C80") (pin "2") (pinfunction "2_2") (pintype "passive"))
      (node (ref "C81") (pin "2") (pinfunction "2_2") (pintype "passive"))
      (node (ref "C82") (pin "2") (pinfunction "2_2") (pintype "passive"))
      (node (ref "C83") (pin "2") (pinfunction "2_2") (pintype "passive"))
      (node (ref "C84") (pin "2") (pinfunction "2_2") (pintype "passive"))
      (node (ref "C85") (pin "2") (pinfunction "2_2") (pintype "passive"))
      (node (ref "C86") (pin "2") (pinfunction "2_2") (pintype "passive"))
      (node (ref "C87") (pin "2") (pinfunction "2_2") (pintype "passive"))
      (node (ref "C88") (pin "2") (pinfunction "2_2") (pintype "passive"))
      (node (ref "C89") (pin "2") (pinfunction "2_2") (pintype "passive"))
      (node (ref "C9") (pin "2") (pinfunction "2_2") (pintype "passive"))
      (node (ref "C90") (pin "2") (pinfunction "2_2") (pintype "passive"))
      (node (ref "C91") (pin "1") (pinfunction "1_1") (pintype "passive"))
      (node (ref "C92") (pin "2") (pinfunction "2_2") (pintype "passive"))
      (node (ref "C93") (pin "2") (pinfunction "2_2") (pintype "passive"))
      (node (ref "GND") (pin "TP") (pinfunction "TP_TP") (pintype "input"))
      (node (ref "GND75") (pin "TP") (pinfunction "TP_TP") (pintype "input"))
      (node (ref "GND77") (pin "TP") (pinfunction "TP_TP") (pintype "input"))
      (node (ref "R12") (pin "2") (pinfunction "2_2") (pintype "passive"))
      (node (ref "R15") (pin "2") (pinfunction "2_2") (pintype "passive"))
      (node (ref "R18") (pin "2") (pinfunction "2_2") (pintype "passive"))
      (node (ref "R22") (pin "1") (pinfunction "1_1") (pintype "passive"))
      (node (ref "R2X") (pin "2") (pinfunction "2_2") (pintype "passive"))
      (node (ref "R3") (pin "2") (pinfunction "2_2") (pintype "passive"))
      (node (ref "R6") (pin "2") (pinfunction "2_2") (pintype "passive"))
      (node (ref "R9") (pin "2") (pinfunction "2_2") (pintype "passive"))
      (node (ref "SENSOR") (pin "A21") (pinfunction "GND_A21") (pintype "power_in"))
      (node (ref "SENSOR") (pin "A25") (pinfunction "GND_A25") (pintype "power_in"))
      (node (ref "SENSOR") (pin "A28") (pinfunction "GND_A28") (pintype "power_in"))
      (node (ref "SENSOR") (pin "A29") (pinfunction "GND_A29") (pintype "power_in"))
      (node (ref "SENSOR") (pin "A9") (pinfunction "GND_A9") (pintype "power_in"))
      (node (ref "SENSOR") (pin "B22") (pinfunction "GND_B22") (pintype "power_in"))
      (node (ref "SENSOR") (pin "B26") (pinfunction "GND_B26") (pintype "power_in"))
      (node (ref "SENSOR") (pin "B27") (pinfunction "GND_B27") (pintype "power_in"))
      (node (ref "SENSOR") (pin "B28") (pinfunction "GND_B28") (pintype "power_in"))
      (node (ref "SENSOR") (pin "B5") (pinfunction "GND_B5") (pintype "power_in"))
      (node (ref "SENSOR") (pin "C15") (pinfunction "GND_C15") (pintype "power_in"))
      (node (ref "SENSOR") (pin "C16") (pinfunction "GND_C16") (pintype "power_in"))
      (node (ref "SENSOR") (pin "C28") (pinfunction "GND_C28") (pintype "power_in"))
      (node (ref "SENSOR") (pin "D2") (pinfunction "GND_D2") (pintype "power_in"))
      (node (ref "SENSOR") (pin "D25") (pinfunction "GND_D25") (pintype "power_in"))
      (node (ref "SENSOR") (pin "D27") (pinfunction "GND_D27") (pintype "power_in"))
      (node (ref "SENSOR") (pin "D29") (pinfunction "GND_D29") (pintype "power_in"))
      (node (ref "SENSOR") (pin "E15") (pinfunction "GND_E15") (pintype "power_in"))
      (node (ref "SENSOR") (pin "E16") (pinfunction "GND_E16") (pintype "power_in"))
      (node (ref "SENSOR") (pin "E25") (pinfunction "GND_E25") (pintype "power_in"))
      (node (ref "SENSOR") (pin "E27") (pinfunction "GND_E27") (pintype "power_in"))
      (node (ref "SENSOR") (pin "E3") (pinfunction "GND_E3") (pintype "power_in"))
      (node (ref "SENSOR") (pin "E4") (pinfunction "DIO2_E4") (pintype "output"))
      (node (ref "SENSOR") (pin "F27") (pinfunction "GND_F27") (pintype "power_in"))
      (node (ref "SENSOR") (pin "F4") (pinfunction "DIO1_F4") (pintype "output"))
      (node (ref "SENSOR") (pin "G3") (pinfunction "DIO4_G3") (pintype "output"))
      (node (ref "SENSOR") (pin "G5") (pinfunction "GND_G5") (pintype "power_in"))
      (node (ref "SENSOR") (pin "H1") (pinfunction "GND_H1") (pintype "power_in"))
      (node (ref "SENSOR") (pin "H21") (pinfunction "GND_H21") (pintype "power_in"))
      (node (ref "SENSOR") (pin "H25") (pinfunction "GND_H25") (pintype "power_in"))
      (node (ref "SENSOR") (pin "H27") (pinfunction "GND_H27") (pintype "power_in"))
      (node (ref "SENSOR") (pin "H4") (pinfunction "DIO3_H4") (pintype "output"))
      (node (ref "SENSOR") (pin "H6") (pinfunction "GND_H6") (pintype "power_in"))
      (node (ref "SENSOR") (pin "H9") (pinfunction "GND_H9") (pintype "power_in"))
      (node (ref "U1") (pin "6") (pinfunction "ANODE_6") (pintype "input"))
      (node (ref "U2") (pin "6") (pinfunction "ANODE_6") (pintype "input"))
      (node (ref "U3") (pin "2") (pinfunction "GND_2") (pintype "power_in"))
      (node (ref "U3") (pin "EP") (pinfunction "EP_EP") (pintype "power_in"))
      (node (ref "U4") (pin "16") (pinfunction "DIR2_16") (pintype "input"))
      (node (ref "U4") (pin "7") (pinfunction "~{OE}_7") (pintype "input"))
      (node (ref "U4") (pin "8") (pinfunction "GND_8") (pintype "passive"))
      (node (ref "U5") (pin "6") (pinfunction "DIR4_6") (pintype "input"))
      (node (ref "U5") (pin "7") (pinfunction "~{OE}_7") (pintype "input"))
      (node (ref "U5") (pin "8") (pinfunction "GND_8") (pintype "passive"))
      (node (ref "U6") (pin "16") (pinfunction "DIR2_16") (pintype "input"))
      (node (ref "U6") (pin "7") (pinfunction "~{OE}_7") (pintype "input"))
      (node (ref "U6") (pin "8") (pinfunction "GND_8") (pintype "passive"))
      (node (ref "U7") (pin "4") (pinfunction "GND_4") (pintype "power_in"))
      (node (ref "U7") (pin "5") (pinfunction "A2_5") (pintype "input"))
      (node (ref "U7") (pin "6") (pinfunction "A1_6") (pintype "input"))
      (node (ref "U7") (pin "7") (pinfunction "A0_7") (pintype "input"))
      (node (ref "UEP") (pin "1") (pinfunction "A0_1") (pintype "input"))
      (node (ref "UEP") (pin "2") (pinfunction "A1_2") (pintype "input"))
      (node (ref "UEP") (pin "3") (pinfunction "A2_3") (pintype "input"))
      (node (ref "UEP") (pin "4") (pinfunction "GND_4") (pintype "passive"))
      (node (ref "UEP") (pin "EP") (pinfunction "EP_EP") (pintype "passive"))
      (node (ref "UNE") (pin "4") (pinfunction "VSS_4") (pintype "power_in"))
      (node (ref "UNE") (pin "EP") (pinfunction "EP_EP") (pintype "passive"))
      (node (ref "UNN") (pin "4") (pinfunction "VSS_4") (pintype "power_in"))
      (node (ref "UNN") (pin "EP") (pinfunction "EP_EP") (pintype "passive"))
      (node (ref "UNW") (pin "4") (pinfunction "VSS_4") (pintype "power_in"))
      (node (ref "UNW") (pin "EP") (pinfunction "EP_EP") (pintype "passive"))
      (node (ref "USE") (pin "4") (pinfunction "VSS_4") (pintype "power_in"))
      (node (ref "USE") (pin "EP") (pinfunction "EP_EP") (pintype "passive"))
      (node (ref "USS") (pin "4") (pinfunction "VSS_4") (pintype "power_in"))
      (node (ref "USS") (pin "EP") (pinfunction "EP_EP") (pintype "passive"))
      (node (ref "USW") (pin "4") (pinfunction "VSS_4") (pintype "power_in"))
      (node (ref "USW") (pin "EP") (pinfunction "EP_EP") (pintype "passive"))
      (node (ref "X-NORTH") (pin "102") (pinfunction "102_102") (pintype "bidirectional"))
      (node (ref "X-NORTH") (pin "103") (pinfunction "103_103") (pintype "bidirectional"))
      (node (ref "X-NORTH") (pin "108") (pinfunction "108_108") (pintype "bidirectional"))
      (node (ref "X-NORTH") (pin "114") (pinfunction "114_114") (pintype "bidirectional"))
      (node (ref "X-NORTH") (pin "12") (pinfunction "12_12") (pintype "bidirectional"))
      (node (ref "X-NORTH") (pin "120") (pinfunction "120_120") (pintype "bidirectional"))
      (node (ref "X-NORTH") (pin "126") (pinfunction "126_126") (pintype "bidirectional"))
      (node (ref "X-NORTH") (pin "132") (pinfunction "132_132") (pintype "bidirectional"))
      (node (ref "X-NORTH") (pin "138") (pinfunction "138_138") (pintype "bidirectional"))
      (node (ref "X-NORTH") (pin "139") (pinfunction "139_139") (pintype "bidirectional"))
      (node (ref "X-NORTH") (pin "18") (pinfunction "18_18") (pintype "bidirectional"))
      (node (ref "X-NORTH") (pin "24") (pinfunction "24_24") (pintype "bidirectional"))
      (node (ref "X-NORTH") (pin "30") (pinfunction "30_30") (pintype "bidirectional"))
      (node (ref "X-NORTH") (pin "36") (pinfunction "36_36") (pintype "bidirectional"))
      (node (ref "X-NORTH") (pin "42") (pinfunction "42_42") (pintype "bidirectional"))
      (node (ref "X-NORTH") (pin "43") (pinfunction "43_43") (pintype "bidirectional"))
      (node (ref "X-NORTH") (pin "48") (pinfunction "48_48") (pintype "bidirectional"))
      (node (ref "X-NORTH") (pin "54") (pinfunction "54_54") (pintype "bidirectional"))
      (node (ref "X-NORTH") (pin "60") (pinfunction "60_60") (pintype "bidirectional"))
      (node (ref "X-NORTH") (pin "66") (pinfunction "66_66") (pintype "bidirectional"))
      (node (ref "X-NORTH") (pin "72") (pinfunction "72_72") (pintype "bidirectional"))
      (node (ref "X-NORTH") (pin "78") (pinfunction "78_78") (pintype "bidirectional"))
      (node (ref "X-NORTH") (pin "84") (pinfunction "84_84") (pintype "bidirectional"))
      (node (ref "X-NORTH") (pin "90") (pinfunction "90_90") (pintype "bidirectional"))
      (node (ref "X-NORTH") (pin "96") (pinfunction "96_96") (pintype "bidirectional"))
      (node (ref "X-SOUTH") (pin "102") (pinfunction "102_102") (pintype "bidirectional"))
      (node (ref "X-SOUTH") (pin "103") (pinfunction "103_103") (pintype "bidirectional"))
      (node (ref "X-SOUTH") (pin "108") (pinfunction "108_108") (pintype "bidirectional"))
      (node (ref "X-SOUTH") (pin "114") (pinfunction "114_114") (pintype "bidirectional"))
      (node (ref "X-SOUTH") (pin "12") (pinfunction "12_12") (pintype "bidirectional"))
      (node (ref "X-SOUTH") (pin "120") (pinfunction "120_120") (pintype "bidirectional"))
      (node (ref "X-SOUTH") (pin "126") (pinfunction "126_126") (pintype "bidirectional"))
      (node (ref "X-SOUTH") (pin "132") (pinfunction "132_132") (pintype "bidirectional"))
      (node (ref "X-SOUTH") (pin "138") (pinfunction "138_138") (pintype "bidirectional"))
      (node (ref "X-SOUTH") (pin "139") (pinfunction "139_139") (pintype "bidirectional"))
      (node (ref "X-SOUTH") (pin "18") (pinfunction "18_18") (pintype "bidirectional"))
      (node (ref "X-SOUTH") (pin "24") (pinfunction "24_24") (pintype "bidirectional"))
      (node (ref "X-SOUTH") (pin "30") (pinfunction "30_30") (pintype "bidirectional"))
      (node (ref "X-SOUTH") (pin "36") (pinfunction "36_36") (pintype "bidirectional"))
      (node (ref "X-SOUTH") (pin "42") (pinfunction "42_42") (pintype "bidirectional"))
      (node (ref "X-SOUTH") (pin "43") (pinfunction "43_43") (pintype "bidirectional"))
      (node (ref "X-SOUTH") (pin "48") (pinfunction "48_48") (pintype "bidirectional"))
      (node (ref "X-SOUTH") (pin "54") (pinfunction "54_54") (pintype "bidirectional"))
      (node (ref "X-SOUTH") (pin "60") (pinfunction "60_60") (pintype "bidirectional"))
      (node (ref "X-SOUTH") (pin "66") (pinfunction "66_66") (pintype "bidirectional"))
      (node (ref "X-SOUTH") (pin "72") (pinfunction "72_72") (pintype "bidirectional"))
      (node (ref "X-SOUTH") (pin "78") (pinfunction "78_78") (pintype "bidirectional"))
      (node (ref "X-SOUTH") (pin "84") (pinfunction "84_84") (pintype "bidirectional"))
      (node (ref "X-SOUTH") (pin "90") (pinfunction "90_90") (pintype "bidirectional"))
      (node (ref "X-SOUTH") (pin "96") (pinfunction "96_96") (pintype "bidirectional"))
    )
    (net (code "4") (name "N$42") (class "Default")
      (node (ref "SENSOR") (pin "A2") (pinfunction "TANA_A2") (pintype "output"))
    )
    (net (code "5") (name "N00_N") (class "Default")
      (node (ref "R25") (pin "2") (pinfunction "2_2") (pintype "passive"))
      (node (ref "SENSOR") (pin "E6") (pinfunction "LVDS_CLK_P_E6") (pintype "input"))
      (node (ref "X-NORTH") (pin "16") (pinfunction "16_16") (pintype "bidirectional"))
    )
    (net (code "6") (name "N00_P") (class "Default")
      (node (ref "R25") (pin "1") (pinfunction "1_1") (pintype "passive"))
      (node (ref "SENSOR") (pin "E5") (pinfunction "LVDS_CLK_N_E5") (pintype "input"))
      (node (ref "X-NORTH") (pin "14") (pinfunction "14_14") (pintype "bidirectional"))
    )
    (net (code "7") (name "N01_N") (class "Default")
      (node (ref "SENSOR") (pin "G7") (pinfunction "OUTCLK_P_G7") (pintype "output"))
      (node (ref "X-NORTH") (pin "17") (pinfunction "17_17") (pintype "bidirectional"))
    )
    (net (code "8") (name "N01_P") (class "Default")
      (node (ref "SENSOR") (pin "G6") (pinfunction "OUTCLK_N_G6") (pintype "output"))
      (node (ref "X-NORTH") (pin "15") (pinfunction "15_15") (pintype "bidirectional"))
    )
    (net (code "9") (name "N02_N") (class "Default")
      (node (ref "SENSOR") (pin "F7") (pinfunction "OUT33_P_F7") (pintype "output"))
      (node (ref "X-NORTH") (pin "22") (pinfunction "22_22") (pintype "bidirectional"))
    )
    (net (code "10") (name "N02_P") (class "Default")
      (node (ref "SENSOR") (pin "F6") (pinfunction "OUT33_N_F6") (pintype "output"))
      (node (ref "X-NORTH") (pin "20") (pinfunction "20_20") (pintype "bidirectional"))
    )
    (net (code "11") (name "N03_N") (class "Default")
      (node (ref "X-NORTH") (pin "23") (pinfunction "23_23") (pintype "bidirectional"))
    )
    (net (code "12") (name "N03_P") (class "Default")
      (node (ref "X-NORTH") (pin "21") (pinfunction "21_21") (pintype "bidirectional"))
    )
    (net (code "13") (name "N04_N") (class "Default")
      (node (ref "SENSOR") (pin "E8") (pinfunction "OUT35_P_E8") (pintype "output"))
      (node (ref "X-NORTH") (pin "28") (pinfunction "28_28") (pintype "bidirectional"))
    )
    (net (code "14") (name "N04_P") (class "Default")
      (node (ref "SENSOR") (pin "E7") (pinfunction "OUT35_N_E7") (pintype "output"))
      (node (ref "X-NORTH") (pin "26") (pinfunction "26_26") (pintype "bidirectional"))
    )
    (net (code "15") (name "N05_N") (class "Default")
      (node (ref "SENSOR") (pin "H8") (pinfunction "OUT34_P_H8") (pintype "output"))
      (node (ref "X-NORTH") (pin "29") (pinfunction "29_29") (pintype "bidirectional"))
    )
    (net (code "16") (name "N05_P") (class "Default")
      (node (ref "SENSOR") (pin "H7") (pinfunction "OUT34_N_H7") (pintype "output"))
      (node (ref "X-NORTH") (pin "27") (pinfunction "27_27") (pintype "bidirectional"))
    )
    (net (code "17") (name "N06_N") (class "Default")
      (node (ref "SENSOR") (pin "F9") (pinfunction "OUT37_P_F9") (pintype "output"))
      (node (ref "X-NORTH") (pin "34") (pinfunction "34_34") (pintype "bidirectional"))
    )
    (net (code "18") (name "N06_P") (class "Default")
      (node (ref "SENSOR") (pin "F8") (pinfunction "OUT37_N_F8") (pintype "output"))
      (node (ref "X-NORTH") (pin "32") (pinfunction "32_32") (pintype "bidirectional"))
    )
    (net (code "19") (name "N07_N") (class "Default")
      (node (ref "SENSOR") (pin "G9") (pinfunction "OUT36_P_G9") (pintype "output"))
      (node (ref "X-NORTH") (pin "35") (pinfunction "35_35") (pintype "bidirectional"))
    )
    (net (code "20") (name "N07_P") (class "Default")
      (node (ref "SENSOR") (pin "G8") (pinfunction "OUT36_N_G8") (pintype "output"))
      (node (ref "X-NORTH") (pin "33") (pinfunction "33_33") (pintype "bidirectional"))
    )
    (net (code "21") (name "N08_N") (class "Default")
      (node (ref "SENSOR") (pin "E10") (pinfunction "OUT38_P_E10") (pintype "output"))
      (node (ref "X-NORTH") (pin "40") (pinfunction "40_40") (pintype "bidirectional"))
    )
    (net (code "22") (name "N08_P") (class "Default")
      (node (ref "SENSOR") (pin "E9") (pinfunction "OUT38_N_E9") (pintype "output"))
      (node (ref "X-NORTH") (pin "38") (pinfunction "38_38") (pintype "bidirectional"))
    )
    (net (code "23") (name "N09_N") (class "Default")
      (node (ref "SENSOR") (pin "G11") (pinfunction "OUT39_P_G11") (pintype "output"))
      (node (ref "X-NORTH") (pin "41") (pinfunction "41_41") (pintype "bidirectional"))
    )
    (net (code "24") (name "N09_P") (class "Default")
      (node (ref "SENSOR") (pin "G10") (pinfunction "OUT39_N_G10") (pintype "output"))
      (node (ref "X-NORTH") (pin "39") (pinfunction "39_39") (pintype "bidirectional"))
    )
    (net (code "25") (name "N10_N") (class "Default")
      (node (ref "SENSOR") (pin "F11") (pinfunction "OUT40_P_F11") (pintype "output"))
      (node (ref "X-NORTH") (pin "46") (pinfunction "46_46") (pintype "bidirectional"))
    )
    (net (code "26") (name "N10_P") (class "Default")
      (node (ref "SENSOR") (pin "F10") (pinfunction "OUT40_N_F10") (pintype "output"))
      (node (ref "X-NORTH") (pin "44") (pinfunction "44_44") (pintype "bidirectional"))
    )
    (net (code "27") (name "N11_N") (class "Default")
      (node (ref "SENSOR") (pin "H12") (pinfunction "OUT41_P_H12") (pintype "output"))
      (node (ref "X-NORTH") (pin "47") (pinfunction "47_47") (pintype "bidirectional"))
    )
    (net (code "28") (name "N11_P") (class "Default")
      (node (ref "SENSOR") (pin "H11") (pinfunction "OUT41_N_H11") (pintype "output"))
      (node (ref "X-NORTH") (pin "45") (pinfunction "45_45") (pintype "bidirectional"))
    )
    (net (code "29") (name "N12_N") (class "Default")
      (node (ref "SENSOR") (pin "E12") (pinfunction "OUT42_P_E12") (pintype "output"))
      (node (ref "X-NORTH") (pin "52") (pinfunction "52_52") (pintype "bidirectional"))
    )
    (net (code "30") (name "N12_P") (class "Default")
      (node (ref "SENSOR") (pin "E11") (pinfunction "OUT42_N_E11") (pintype "output"))
      (node (ref "X-NORTH") (pin "50") (pinfunction "50_50") (pintype "bidirectional"))
    )
    (net (code "31") (name "N13_N") (class "Default")
      (node (ref "SENSOR") (pin "G13") (pinfunction "OUT43_P_G13") (pintype "output"))
      (node (ref "X-NORTH") (pin "53") (pinfunction "53_53") (pintype "bidirectional"))
    )
    (net (code "32") (name "N13_P") (class "Default")
      (node (ref "SENSOR") (pin "G12") (pinfunction "OUT43_N_G12") (pintype "output"))
      (node (ref "X-NORTH") (pin "51") (pinfunction "51_51") (pintype "bidirectional"))
    )
    (net (code "33") (name "N14_N") (class "Default")
      (node (ref "SENSOR") (pin "F13") (pinfunction "OUT44_P_F13") (pintype "output"))
      (node (ref "X-NORTH") (pin "58") (pinfunction "58_58") (pintype "bidirectional"))
    )
    (net (code "34") (name "N14_P") (class "Default")
      (node (ref "SENSOR") (pin "F12") (pinfunction "OUT44_N_F12") (pintype "output"))
      (node (ref "X-NORTH") (pin "56") (pinfunction "56_56") (pintype "bidirectional"))
    )
    (net (code "35") (name "N15_N") (class "Default")
      (node (ref "SENSOR") (pin "H14") (pinfunction "OUT45_P_H14") (pintype "output"))
      (node (ref "X-NORTH") (pin "59") (pinfunction "59_59") (pintype "bidirectional"))
    )
    (net (code "36") (name "N15_P") (class "Default")
      (node (ref "SENSOR") (pin "H13") (pinfunction "OUT45_N_H13") (pintype "output"))
      (node (ref "X-NORTH") (pin "57") (pinfunction "57_57") (pintype "bidirectional"))
    )
    (net (code "37") (name "N16_N") (class "Default")
      (node (ref "SENSOR") (pin "E14") (pinfunction "OUT46_P_E14") (pintype "output"))
      (node (ref "X-NORTH") (pin "64") (pinfunction "64_64") (pintype "bidirectional"))
    )
    (net (code "38") (name "N16_P") (class "Default")
      (node (ref "SENSOR") (pin "E13") (pinfunction "OUT46_N_E13") (pintype "output"))
      (node (ref "X-NORTH") (pin "62") (pinfunction "62_62") (pintype "bidirectional"))
    )
    (net (code "39") (name "N17_N") (class "Default")
      (node (ref "SENSOR") (pin "G15") (pinfunction "OUT47_P_G15") (pintype "output"))
      (node (ref "X-NORTH") (pin "65") (pinfunction "65_65") (pintype "bidirectional"))
    )
    (net (code "40") (name "N17_P") (class "Default")
      (node (ref "SENSOR") (pin "G14") (pinfunction "OUT47_N_G14") (pintype "output"))
      (node (ref "X-NORTH") (pin "63") (pinfunction "63_63") (pintype "bidirectional"))
    )
    (net (code "41") (name "N18_N") (class "Default")
      (node (ref "SENSOR") (pin "F15") (pinfunction "OUT48_P_F15") (pintype "output"))
      (node (ref "X-NORTH") (pin "70") (pinfunction "70_70") (pintype "bidirectional"))
    )
    (net (code "42") (name "N18_P") (class "Default")
      (node (ref "SENSOR") (pin "F14") (pinfunction "OUT48_N_F14") (pintype "output"))
      (node (ref "X-NORTH") (pin "68") (pinfunction "68_68") (pintype "bidirectional"))
    )
    (net (code "43") (name "N19_N") (class "Default")
      (node (ref "SENSOR") (pin "G17") (pinfunction "OUT50_P_G17") (pintype "output"))
      (node (ref "X-NORTH") (pin "71") (pinfunction "71_71") (pintype "bidirectional"))
    )
    (net (code "44") (name "N19_P") (class "Default")
      (node (ref "SENSOR") (pin "G16") (pinfunction "OUT50_N_G16") (pintype "output"))
      (node (ref "X-NORTH") (pin "69") (pinfunction "69_69") (pintype "bidirectional"))
    )
    (net (code "45") (name "N20_N") (class "Default")
      (node (ref "SENSOR") (pin "F17") (pinfunction "OUT49_P_F17") (pintype "output"))
      (node (ref "X-NORTH") (pin "76") (pinfunction "76_76") (pintype "bidirectional"))
    )
    (net (code "46") (name "N20_P") (class "Default")
      (node (ref "SENSOR") (pin "F16") (pinfunction "OUT49_N_F16") (pintype "output"))
      (node (ref "X-NORTH") (pin "74") (pinfunction "74_74") (pintype "bidirectional"))
    )
    (net (code "47") (name "N21_N") (class "Default")
      (node (ref "SENSOR") (pin "H18") (pinfunction "OUT52_P_H18") (pintype "output"))
      (node (ref "X-NORTH") (pin "77") (pinfunction "77_77") (pintype "bidirectional"))
    )
    (net (code "48") (name "N21_P") (class "Default")
      (node (ref "SENSOR") (pin "H17") (pinfunction "OUT52_N_H17") (pintype "output"))
      (node (ref "X-NORTH") (pin "75") (pinfunction "75_75") (pintype "bidirectional"))
    )
    (net (code "49") (name "N22_N") (class "Default")
      (node (ref "SENSOR") (pin "E18") (pinfunction "OUT51_P_E18") (pintype "output"))
      (node (ref "X-NORTH") (pin "82") (pinfunction "82_82") (pintype "bidirectional"))
    )
    (net (code "50") (name "N22_P") (class "Default")
      (node (ref "SENSOR") (pin "E17") (pinfunction "OUT51_N_E17") (pintype "output"))
      (node (ref "X-NORTH") (pin "80") (pinfunction "80_80") (pintype "bidirectional"))
    )
    (net (code "51") (name "N23_N") (class "Default")
      (node (ref "SENSOR") (pin "G19") (pinfunction "OUT54_P_G19") (pintype "output"))
      (node (ref "X-NORTH") (pin "83") (pinfunction "83_83") (pintype "bidirectional"))
    )
    (net (code "52") (name "N23_P") (class "Default")
      (node (ref "SENSOR") (pin "G18") (pinfunction "OUT54_N_G18") (pintype "output"))
      (node (ref "X-NORTH") (pin "81") (pinfunction "81_81") (pintype "bidirectional"))
    )
    (net (code "53") (name "N24_N") (class "Default")
      (node (ref "SENSOR") (pin "F19") (pinfunction "OUT53_P_F19") (pintype "output"))
      (node (ref "X-NORTH") (pin "88") (pinfunction "88_88") (pintype "bidirectional"))
    )
    (net (code "54") (name "N24_P") (class "Default")
      (node (ref "SENSOR") (pin "F18") (pinfunction "OUT53_N_F18") (pintype "output"))
      (node (ref "X-NORTH") (pin "86") (pinfunction "86_86") (pintype "bidirectional"))
    )
    (net (code "55") (name "N25_N") (class "Default")
      (node (ref "SENSOR") (pin "H20") (pinfunction "OUT56_P_H20") (pintype "output"))
      (node (ref "X-NORTH") (pin "89") (pinfunction "89_89") (pintype "bidirectional"))
    )
    (net (code "56") (name "N25_P") (class "Default")
      (node (ref "SENSOR") (pin "H19") (pinfunction "OUT56_N_H19") (pintype "output"))
      (node (ref "X-NORTH") (pin "87") (pinfunction "87_87") (pintype "bidirectional"))
    )
    (net (code "57") (name "N26_N") (class "Default")
      (node (ref "SENSOR") (pin "E20") (pinfunction "OUT55_P_E20") (pintype "output"))
      (node (ref "X-NORTH") (pin "94") (pinfunction "94_94") (pintype "bidirectional"))
    )
    (net (code "58") (name "N26_P") (class "Default")
      (node (ref "SENSOR") (pin "E19") (pinfunction "OUT55_N_E19") (pintype "output"))
      (node (ref "X-NORTH") (pin "92") (pinfunction "92_92") (pintype "bidirectional"))
    )
    (net (code "59") (name "N27_N") (class "Default")
      (node (ref "SENSOR") (pin "G21") (pinfunction "OUT58_P_G21") (pintype "output"))
      (node (ref "X-NORTH") (pin "95") (pinfunction "95_95") (pintype "bidirectional"))
    )
    (net (code "60") (name "N27_P") (class "Default")
      (node (ref "SENSOR") (pin "G20") (pinfunction "OUT58_N_G20") (pintype "output"))
      (node (ref "X-NORTH") (pin "93") (pinfunction "93_93") (pintype "bidirectional"))
    )
    (net (code "61") (name "N28_N") (class "Default")
      (node (ref "SENSOR") (pin "F21") (pinfunction "OUT57_P_F21") (pintype "output"))
      (node (ref "X-NORTH") (pin "100") (pinfunction "100_100") (pintype "bidirectional"))
    )
    (net (code "62") (name "N28_P") (class "Default")
      (node (ref "SENSOR") (pin "F20") (pinfunction "OUT57_N_F20") (pintype "output"))
      (node (ref "X-NORTH") (pin "98") (pinfunction "98_98") (pintype "bidirectional"))
    )
    (net (code "63") (name "N29_N") (class "Default")
      (node (ref "SENSOR") (pin "G23") (pinfunction "OUT61_P_G23") (pintype "output"))
      (node (ref "X-NORTH") (pin "101") (pinfunction "101_101") (pintype "bidirectional"))
    )
    (net (code "64") (name "N29_P") (class "Default")
      (node (ref "SENSOR") (pin "G22") (pinfunction "OUT61_N_G22") (pintype "output"))
      (node (ref "X-NORTH") (pin "99") (pinfunction "99_99") (pintype "bidirectional"))
    )
    (net (code "65") (name "N30_N") (class "Default")
      (node (ref "SENSOR") (pin "E22") (pinfunction "OUT59_P_E22") (pintype "output"))
      (node (ref "X-NORTH") (pin "106") (pinfunction "106_106") (pintype "bidirectional"))
    )
    (net (code "66") (name "N30_P") (class "Default")
      (node (ref "SENSOR") (pin "E21") (pinfunction "OUT59_N_E21") (pintype "output"))
      (node (ref "X-NORTH") (pin "104") (pinfunction "104_104") (pintype "bidirectional"))
    )
    (net (code "67") (name "N31_N") (class "Default")
      (node (ref "SENSOR") (pin "H24") (pinfunction "OUT63_P_H24") (pintype "output"))
      (node (ref "X-NORTH") (pin "107") (pinfunction "107_107") (pintype "bidirectional"))
    )
    (net (code "68") (name "N31_P") (class "Default")
      (node (ref "SENSOR") (pin "H23") (pinfunction "OUT63_N_H23") (pintype "output"))
      (node (ref "X-NORTH") (pin "105") (pinfunction "105_105") (pintype "bidirectional"))
    )
    (net (code "69") (name "N32_N") (class "Default")
      (node (ref "SENSOR") (pin "F23") (pinfunction "OUT60_P_F23") (pintype "output"))
      (node (ref "X-NORTH") (pin "112") (pinfunction "112_112") (pintype "bidirectional"))
    )
    (net (code "70") (name "N32_P") (class "Default")
      (node (ref "SENSOR") (pin "F22") (pinfunction "OUT60_N_F22") (pintype "output"))
      (node (ref "X-NORTH") (pin "110") (pinfunction "110_110") (pintype "bidirectional"))
    )
    (net (code "71") (name "N33_N") (class "Default")
      (node (ref "SENSOR") (pin "G25") (pinfunction "OUT64_P_G25") (pintype "output"))
      (node (ref "X-NORTH") (pin "113") (pinfunction "113_113") (pintype "bidirectional"))
    )
    (net (code "72") (name "N33_P") (class "Default")
      (node (ref "SENSOR") (pin "G24") (pinfunction "OUT64_N_G24") (pintype "output"))
      (node (ref "X-NORTH") (pin "111") (pinfunction "111_111") (pintype "bidirectional"))
    )
    (net (code "73") (name "N34_N") (class "Default")
      (node (ref "SENSOR") (pin "E24") (pinfunction "OUT62_P_E24") (pintype "output"))
      (node (ref "X-NORTH") (pin "118") (pinfunction "118_118") (pintype "bidirectional"))
    )
    (net (code "74") (name "N34_P") (class "Default")
      (node (ref "SENSOR") (pin "E23") (pinfunction "OUT62_N_E23") (pintype "output"))
      (node (ref "X-NORTH") (pin "116") (pinfunction "116_116") (pintype "bidirectional"))
    )
    (net (code "75") (name "N35_N") (class "Default")
      (node (ref "U6") (pin "4") (pinfunction "A4_4") (pintype "bidirectional"))
      (node (ref "X-NORTH") (pin "119") (pinfunction "119_119") (pintype "bidirectional"))
    )
    (net (code "76") (name "N35_P") (class "Default")
      (node (ref "U6") (pin "3") (pinfunction "A3_3") (pintype "bidirectional"))
      (node (ref "X-NORTH") (pin "117") (pinfunction "117_117") (pintype "bidirectional"))
    )
    (net (code "77") (name "N36_N") (class "Default")
      (node (ref "X-NORTH") (pin "124") (pinfunction "124_124") (pintype "bidirectional"))
    )
    (net (code "78") (name "N36_P") (class "Default")
      (node (ref "X-NORTH") (pin "122") (pinfunction "122_122") (pintype "bidirectional"))
    )
    (net (code "79") (name "N37_N") (class "Default")
      (node (ref "U5") (pin "3") (pinfunction "A3_3") (pintype "bidirectional"))
      (node (ref "X-NORTH") (pin "125") (pinfunction "125_125") (pintype "bidirectional"))
    )
    (net (code "80") (name "N37_P") (class "Default")
      (node (ref "U5") (pin "4") (pinfunction "A4_4") (pintype "bidirectional"))
      (node (ref "X-NORTH") (pin "123") (pinfunction "123_123") (pintype "bidirectional"))
    )
    (net (code "81") (name "N38_N") (class "Default")
      (node (ref "U6") (pin "2") (pinfunction "A2_2") (pintype "bidirectional"))
      (node (ref "X-NORTH") (pin "130") (pinfunction "130_130") (pintype "bidirectional"))
    )
    (net (code "82") (name "N38_P") (class "Default")
      (node (ref "U6") (pin "1") (pinfunction "A1_1") (pintype "bidirectional"))
      (node (ref "X-NORTH") (pin "128") (pinfunction "128_128") (pintype "bidirectional"))
    )
    (net (code "83") (name "N39_N") (class "Default")
      (node (ref "U5") (pin "1") (pinfunction "A1_1") (pintype "bidirectional"))
      (node (ref "X-NORTH") (pin "131") (pinfunction "131_131") (pintype "bidirectional"))
    )
    (net (code "84") (name "N39_P") (class "Default")
      (node (ref "U5") (pin "2") (pinfunction "A2_2") (pintype "bidirectional"))
      (node (ref "X-NORTH") (pin "129") (pinfunction "129_129") (pintype "bidirectional"))
    )
    (net (code "85") (name "N_CHK_EN") (class "Default")
      (node (ref "X-NORTH") (pin "8") (pinfunction "8_8") (pintype "bidirectional"))
    )
    (net (code "86") (name "N_CHK_V") (class "Default")
      (node (ref "C2") (pin "1") (pinfunction "1_1") (pintype "passive"))
      (node (ref "C3") (pin "1") (pinfunction "1_1") (pintype "passive"))
      (node (ref "C4") (pin "1") (pinfunction "1_1") (pintype "passive"))
      (node (ref "R19") (pin "1") (pinfunction "1_1") (pintype "passive"))
      (node (ref "TP1") (pin "TP") (pinfunction "TP_TP") (pintype "input"))
      (node (ref "UNE") (pin "8") (pinfunction "VDD_8") (pintype "power_in"))
      (node (ref "UNN") (pin "8") (pinfunction "VDD_8") (pintype "power_in"))
      (node (ref "UNW") (pin "8") (pinfunction "VDD_8") (pintype "power_in"))
      (node (ref "X-NORTH") (pin "10") (pinfunction "10_10") (pintype "bidirectional"))
    )
    (net (code "87") (name "N_I2C_EN") (class "Default")
      (node (ref "X-NORTH") (pin "137") (pinfunction "137_137") (pintype "bidirectional"))
    )
    (net (code "88") (name "N_I2C_V") (class "Default")
      (node (ref "C1") (pin "1") (pinfunction "1_1") (pintype "passive"))
      (node (ref "R1X") (pin "1") (pinfunction "1_1") (pintype "passive"))
      (node (ref "UEP") (pin "8") (pinfunction "VCC_8") (pintype "power_in"))
      (node (ref "X-NORTH") (pin "135") (pinfunction "135_135") (pintype "bidirectional"))
    )
    (net (code "89") (name "N_REF") (class "Default")
      (node (ref "R19") (pin "2") (pinfunction "2_2") (pintype "passive"))
      (node (ref "TP2") (pin "TP") (pinfunction "TP_TP") (pintype "input"))
      (node (ref "U1") (pin "1") (pinfunction "CATHODE_1") (pintype "output"))
      (node (ref "U1") (pin "3") (pinfunction "REF_3") (pintype "input"))
      (node (ref "UNE") (pin "2") (pinfunction "VINA-_2") (pintype "input"))
      (node (ref "UNE") (pin "5") (pinfunction "VINB+_5") (pintype "input"))
      (node (ref "UNN") (pin "2") (pinfunction "VINA-_2") (pintype "input"))
      (node (ref "UNN") (pin "5") (pinfunction "VINB+_5") (pintype "input"))
      (node (ref "UNW") (pin "2") (pinfunction "VINA-_2") (pintype "input"))
      (node (ref "UNW") (pin "5") (pinfunction "VINB+_5") (pintype "input"))
    )
    (net (code "90") (name "N_SCK") (class "Default")
      (node (ref "U4") (pin "4") (pinfunction "A4_4") (pintype "bidirectional"))
      (node (ref "X-NORTH") (pin "144") (pinfunction "144_144") (pintype "bidirectional"))
    )
    (net (code "91") (name "N_SCL") (class "Default")
      (node (ref "UEP") (pin "6") (pinfunction "SCL_6") (pintype "input"))
      (node (ref "X-NORTH") (pin "143") (pinfunction "143_143") (pintype "bidirectional"))
    )
    (net (code "92") (name "N_SDA") (class "Default")
      (node (ref "UEP") (pin "5") (pinfunction "SDA_5") (pintype "bidirectional"))
      (node (ref "X-NORTH") (pin "141") (pinfunction "141_141") (pintype "bidirectional"))
    )
    (net (code "93") (name "N_SDI") (class "Default")
      (node (ref "U4") (pin "2") (pinfunction "A2_2") (pintype "bidirectional"))
      (node (ref "X-NORTH") (pin "140") (pinfunction "140_140") (pintype "bidirectional"))
    )
    (net (code "94") (name "N_SDO") (class "Default")
      (node (ref "U4") (pin "3") (pinfunction "A3_3") (pintype "bidirectional"))
      (node (ref "X-NORTH") (pin "142") (pinfunction "142_142") (pintype "bidirectional"))
    )
    (net (code "95") (name "N_SPI_EN") (class "Default")
      (node (ref "U4") (pin "1") (pinfunction "A1_1") (pintype "bidirectional"))
      (node (ref "X-NORTH") (pin "136") (pinfunction "136_136") (pintype "bidirectional"))
    )
    (net (code "96") (name "N_SPI_V") (class "Default")
      (node (ref "C59") (pin "1") (pinfunction "1_1") (pintype "passive"))
      (node (ref "U4") (pin "14") (pinfunction "VCCA_14") (pintype "power_in"))
      (node (ref "U4") (pin "15") (pinfunction "DIR1_15") (pintype "input"))
      (node (ref "U4") (pin "5") (pinfunction "DIR3_5") (pintype "input"))
      (node (ref "U4") (pin "6") (pinfunction "DIR4_6") (pintype "input"))
      (node (ref "X-NORTH") (pin "134") (pinfunction "134_134") (pintype "bidirectional"))
    )
    (net (code "97") (name "N_VE") (class "Default")
      (node (ref "C50") (pin "1") (pinfunction "1_1") (pintype "passive"))
      (node (ref "C51") (pin "1") (pinfunction "1_1") (pintype "passive"))
      (node (ref "C52") (pin "1") (pinfunction "1_1") (pintype "passive"))
      (node (ref "C53") (pin "1") (pinfunction "1_1") (pintype "passive"))
      (node (ref "C54") (pin "1") (pinfunction "1_1") (pintype "passive"))
      (node (ref "C55") (pin "1") (pinfunction "1_1") (pintype "passive"))
      (node (ref "C56") (pin "1") (pinfunction "1_1") (pintype "passive"))
      (node (ref "C67") (pin "1") (pinfunction "1_1") (pintype "passive"))
      (node (ref "C69") (pin "1") (pinfunction "1_1") (pintype "passive"))
      (node (ref "C75") (pin "1") (pinfunction "1_1") (pintype "passive"))
      (node (ref "C76") (pin "1") (pinfunction "1_1") (pintype "passive"))
      (node (ref "C77") (pin "1") (pinfunction "1_1") (pintype "passive"))
      (node (ref "C84") (pin "1") (pinfunction "1_1") (pintype "passive"))
      (node (ref "C85") (pin "1") (pinfunction "1_1") (pintype "passive"))
      (node (ref "C86") (pin "1") (pinfunction "1_1") (pintype "passive"))
      (node (ref "C93") (pin "1") (pinfunction "1_1") (pintype "passive"))
      (node (ref "SENSOR") (pin "C26") (pinfunction "VDD33_C26") (pintype "power_in"))
      (node (ref "SENSOR") (pin "C27") (pinfunction "VDD33_C27") (pintype "power_in"))
      (node (ref "SENSOR") (pin "D26") (pinfunction "VDD33_D26") (pintype "power_in"))
      (node (ref "SENSOR") (pin "D3") (pinfunction "VDD33_D3") (pintype "power_in"))
      (node (ref "SENSOR") (pin "E26") (pinfunction "VDD33_E26") (pintype "power_in"))
      (node (ref "SENSOR") (pin "F26") (pinfunction "VDD33_F26") (pintype "power_in"))
      (node (ref "SENSOR") (pin "F5") (pinfunction "VDD33_F5") (pintype "power_in"))
      (node (ref "TP7") (pin "TP") (pinfunction "TP_TP") (pintype "input"))
      (node (ref "U4") (pin "13") (pinfunction "VCCB_13") (pintype "power_in"))
      (node (ref "U5") (pin "13") (pinfunction "VCCB_13") (pintype "power_in"))
      (node (ref "U6") (pin "13") (pinfunction "VCCB_13") (pintype "power_in"))
      (node (ref "X-NORTH") (pin "109") (pinfunction "109_109") (pintype "bidirectional"))
      (node (ref "X-NORTH") (pin "115") (pinfunction "115_115") (pintype "bidirectional"))
      (node (ref "X-NORTH") (pin "121") (pinfunction "121_121") (pintype "bidirectional"))
      (node (ref "X-NORTH") (pin "127") (pinfunction "127_127") (pintype "bidirectional"))
      (node (ref "X-NORTH") (pin "133") (pinfunction "133_133") (pintype "bidirectional"))
    )
    (net (code "98") (name "N_VE_CV") (class "Default")
      (node (ref "C10") (pin "1") (pinfunction "1_1") (pintype "passive"))
      (node (ref "R7") (pin "1") (pinfunction "1_1") (pintype "passive"))
      (node (ref "X-NORTH") (pin "6") (pinfunction "6_6") (pintype "bidirectional"))
    )
    (net (code "99") (name "N_VE_OV") (class "Default")
      (node (ref "UNE") (pin "7") (pinfunction "OUTB_7") (pintype "output"))
      (node (ref "X-NORTH") (pin "5") (pinfunction "5_5") (pintype "bidirectional"))
    )
    (net (code "100") (name "N_VE_UV") (class "Default")
      (node (ref "UNE") (pin "1") (pinfunction "OUTA_1") (pintype "output"))
      (node (ref "X-NORTH") (pin "11") (pinfunction "11_11") (pintype "bidirectional"))
    )
    (net (code "101") (name "N_VN") (class "Default")
      (node (ref "C31") (pin "1") (pinfunction "1_1") (pintype "passive"))
      (node (ref "C32") (pin "1") (pinfunction "1_1") (pintype "passive"))
      (node (ref "C33") (pin "1") (pinfunction "1_1") (pintype "passive"))
      (node (ref "C34") (pin "1") (pinfunction "1_1") (pintype "passive"))
      (node (ref "C35") (pin "1") (pinfunction "1_1") (pintype "passive"))
      (node (ref "C36") (pin "1") (pinfunction "1_1") (pintype "passive"))
      (node (ref "C37") (pin "1") (pinfunction "1_1") (pintype "passive"))
      (node (ref "C38") (pin "1") (pinfunction "1_1") (pintype "passive"))
      (node (ref "C39") (pin "1") (pinfunction "1_1") (pintype "passive"))
      (node (ref "C40") (pin "1") (pinfunction "1_1") (pintype "passive"))
      (node (ref "C41") (pin "1") (pinfunction "1_1") (pintype "passive"))
      (node (ref "C42") (pin "1") (pinfunction "1_1") (pintype "passive"))
      (node (ref "C43") (pin "1") (pinfunction "1_1") (pintype "passive"))
      (node (ref "C44") (pin "1") (pinfunction "1_1") (pintype "passive"))
      (node (ref "C68") (pin "1") (pinfunction "1_1") (pintype "passive"))
      (node (ref "C70") (pin "1") (pinfunction "1_1") (pintype "passive"))
      (node (ref "C78") (pin "1") (pinfunction "1_1") (pintype "passive"))
      (node (ref "C79") (pin "1") (pinfunction "1_1") (pintype "passive"))
      (node (ref "C80") (pin "1") (pinfunction "1_1") (pintype "passive"))
      (node (ref "C87") (pin "1") (pinfunction "1_1") (pintype "passive"))
      (node (ref "C88") (pin "1") (pinfunction "1_1") (pintype "passive"))
      (node (ref "C89") (pin "1") (pinfunction "1_1") (pintype "passive"))
      (node (ref "SENSOR") (pin "A10") (pinfunction "VDD18_A10") (pintype "power_in"))
      (node (ref "SENSOR") (pin "A15") (pinfunction "VDD18_A15") (pintype "power_in"))
      (node (ref "SENSOR") (pin "A16") (pinfunction "VDD18_A16") (pintype "power_in"))
      (node (ref "SENSOR") (pin "A22") (pinfunction "VDD18_A22") (pintype "power_in"))
      (node (ref "SENSOR") (pin "A26") (pinfunction "VDD18_A26") (pintype "power_in"))
      (node (ref "SENSOR") (pin "A27") (pinfunction "VDD18_A27") (pintype "power_in"))
      (node (ref "SENSOR") (pin "B4") (pinfunction "VDD18_B4") (pintype "power_in"))
      (node (ref "SENSOR") (pin "E1") (pinfunction "VDD18_PLL_E1") (pintype "power_in"))
      (node (ref "SENSOR") (pin "H10") (pinfunction "VDD18_H10") (pintype "power_in"))
      (node (ref "SENSOR") (pin "H15") (pinfunction "VDD18_H15") (pintype "power_in"))
      (node (ref "SENSOR") (pin "H16") (pinfunction "VDD18_H16") (pintype "power_in"))
      (node (ref "SENSOR") (pin "H22") (pinfunction "VDD18_H22") (pintype "power_in"))
      (node (ref "SENSOR") (pin "H26") (pinfunction "VDD18_H26") (pintype "power_in"))
      (node (ref "SENSOR") (pin "H5") (pinfunction "VDD18_H5") (pintype "power_in"))
      (node (ref "TP5") (pin "TP") (pinfunction "TP_TP") (pintype "input"))
      (node (ref "U5") (pin "14") (pinfunction "VCCA_14") (pintype "power_in"))
      (node (ref "U5") (pin "15") (pinfunction "DIR1_15") (pintype "input"))
      (node (ref "U5") (pin "16") (pinfunction "DIR2_16") (pintype "input"))
      (node (ref "U5") (pin "5") (pinfunction "DIR3_5") (pintype "input"))
      (node (ref "U6") (pin "14") (pinfunction "VCCA_14") (pintype "power_in"))
      (node (ref "U6") (pin "15") (pinfunction "DIR1_15") (pintype "input"))
      (node (ref "U6") (pin "5") (pinfunction "DIR3_5") (pintype "input"))
      (node (ref "U6") (pin "6") (pinfunction "DIR4_6") (pintype "input"))
      (node (ref "X-NORTH") (pin "49") (pinfunction "49_49") (pintype "bidirectional"))
      (node (ref "X-NORTH") (pin "55") (pinfunction "55_55") (pintype "bidirectional"))
      (node (ref "X-NORTH") (pin "61") (pinfunction "61_61") (pintype "bidirectional"))
      (node (ref "X-NORTH") (pin "67") (pinfunction "67_67") (pintype "bidirectional"))
      (node (ref "X-NORTH") (pin "73") (pinfunction "73_73") (pintype "bidirectional"))
      (node (ref "X-NORTH") (pin "79") (pinfunction "79_79") (pintype "bidirectional"))
      (node (ref "X-NORTH") (pin "85") (pinfunction "85_85") (pintype "bidirectional"))
      (node (ref "X-NORTH") (pin "91") (pinfunction "91_91") (pintype "bidirectional"))
      (node (ref "X-NORTH") (pin "97") (pinfunction "97_97") (pintype "bidirectional"))
    )
    (net (code "102") (name "N_VN_CV") (class "Default")
      (node (ref "C9") (pin "1") (pinfunction "1_1") (pintype "passive"))
      (node (ref "R4") (pin "1") (pinfunction "1_1") (pintype "passive"))
      (node (ref "X-NORTH") (pin "4") (pinfunction "4_4") (pintype "bidirectional"))
    )
    (net (code "103") (name "N_VN_OV") (class "Default")
      (node (ref "UNN") (pin "7") (pinfunction "OUTB_7") (pintype "output"))
      (node (ref "X-NORTH") (pin "3") (pinfunction "3_3") (pintype "bidirectional"))
    )
    (net (code "104") (name "N_VN_UV") (class "Default")
      (node (ref "UNN") (pin "1") (pinfunction "OUTA_1") (pintype "output"))
      (node (ref "X-NORTH") (pin "9") (pinfunction "9_9") (pintype "bidirectional"))
    )
    (net (code "105") (name "N_VW") (class "Default")
      (node (ref "C57") (pin "1") (pinfunction "1_1") (pintype "passive"))
      (node (ref "C58") (pin "1") (pinfunction "1_1") (pintype "passive"))
      (node (ref "C92") (pin "1") (pinfunction "1_1") (pintype "passive"))
      (node (ref "SENSOR") (pin "E2") (pinfunction "VDD_RES_E2") (pintype "power_in"))
      (node (ref "SENSOR") (pin "G4") (pinfunction "VDD_RES_G4") (pintype "power_in"))
      (node (ref "TP8") (pin "TP") (pinfunction "TP_TP") (pintype "input"))
      (node (ref "X-NORTH") (pin "13") (pinfunction "13_13") (pintype "bidirectional"))
      (node (ref "X-NORTH") (pin "19") (pinfunction "19_19") (pintype "bidirectional"))
      (node (ref "X-NORTH") (pin "25") (pinfunction "25_25") (pintype "bidirectional"))
      (node (ref "X-NORTH") (pin "31") (pinfunction "31_31") (pintype "bidirectional"))
      (node (ref "X-NORTH") (pin "37") (pinfunction "37_37") (pintype "bidirectional"))
    )
    (net (code "106") (name "N_VW_CV") (class "Default")
      (node (ref "C8") (pin "1") (pinfunction "1_1") (pintype "passive"))
      (node (ref "R1") (pin "1") (pinfunction "1_1") (pintype "passive"))
      (node (ref "X-NORTH") (pin "2") (pinfunction "2_2") (pintype "bidirectional"))
    )
    (net (code "107") (name "N_VW_OV") (class "Default")
      (node (ref "UNW") (pin "7") (pinfunction "OUTB_7") (pintype "output"))
      (node (ref "X-NORTH") (pin "1") (pinfunction "1_1") (pintype "bidirectional"))
    )
    (net (code "108") (name "N_VW_UV") (class "Default")
      (node (ref "UNW") (pin "1") (pinfunction "OUTA_1") (pintype "output"))
      (node (ref "X-NORTH") (pin "7") (pinfunction "7_7") (pintype "bidirectional"))
    )
    (net (code "109") (name "Net-(SENSORB-CMDN)") (class "Default")
      (node (ref "C61") (pin "1") (pinfunction "1_1") (pintype "passive"))
      (node (ref "SENSOR") (pin "F1") (pinfunction "CMDN_F1") (pintype "bidirectional"))
    )
    (net (code "110") (name "Net-(SENSORB-CMDP)") (class "Default")
      (node (ref "C22") (pin "2") (pinfunction "2_2") (pintype "passive"))
      (node (ref "SENSOR") (pin "F2") (pinfunction "CMDP_F2") (pintype "bidirectional"))
    )
    (net (code "111") (name "Net-(SENSORB-CMDP_COMP)") (class "Default")
      (node (ref "C28") (pin "2") (pinfunction "2_2") (pintype "passive"))
      (node (ref "SENSOR") (pin "H3") (pinfunction "CMDP_COMP_H3") (pintype "bidirectional"))
    )
    (net (code "112") (name "Net-(SENSORB-CMDP_COMP_INV)") (class "Default")
      (node (ref "C27") (pin "2") (pinfunction "2_2") (pintype "passive"))
      (node (ref "SENSOR") (pin "F3") (pinfunction "CMDP_COMP_INV_F3") (pintype "bidirectional"))
    )
    (net (code "113") (name "Net-(SENSORB-CMD_COLAMP)") (class "Default")
      (node (ref "C25") (pin "2") (pinfunction "2_2") (pintype "passive"))
      (node (ref "SENSOR") (pin "C6") (pinfunction "CMD_COLAMP_C6") (pintype "bidirectional"))
    )
    (net (code "114") (name "Net-(SENSORB-CMD_COL_LOAD)") (class "Default")
      (node (ref "C23") (pin "2") (pinfunction "2_2") (pintype "passive"))
      (node (ref "SENSOR") (pin "B1") (pinfunction "CMD_COL_LOAD_B1") (pintype "bidirectional"))
    )
    (net (code "115") (name "Net-(SENSORB-CMD_COL_PC)") (class "Default")
      (node (ref "C26") (pin "2") (pinfunction "2_2") (pintype "passive"))
      (node (ref "SENSOR") (pin "D1") (pinfunction "CMD_COL_PC_D1") (pintype "bidirectional"))
    )
    (net (code "116") (name "Net-(SENSORB-CMD_LVDS)") (class "Default")
      (node (ref "C62") (pin "1") (pinfunction "1_1") (pintype "passive"))
      (node (ref "SENSOR") (pin "C1") (pinfunction "CMD_LVDS_C1") (pintype "bidirectional"))
    )
    (net (code "117") (name "Net-(SENSORB-CMD_RAMP)") (class "Default")
      (node (ref "C24") (pin "2") (pinfunction "2_2") (pintype "passive"))
      (node (ref "SENSOR") (pin "B29") (pinfunction "CMD_RAMP_B29") (pintype "bidirectional"))
    )
    (net (code "118") (name "Net-(SENSORB-VBGAP)") (class "Default")
      (node (ref "C64") (pin "1") (pinfunction "1_1") (pintype "passive"))
      (node (ref "SENSOR") (pin "C29") (pinfunction "VBGAP_C29") (pintype "bidirectional"))
    )
    (net (code "119") (name "Net-(SENSORB-VCLAMP)") (class "Default")
      (node (ref "C63") (pin "1") (pinfunction "1_1") (pintype "passive"))
      (node (ref "SENSOR") (pin "D4") (pinfunction "VCLAMP_D4") (pintype "bidirectional"))
    )
    (net (code "120") (name "Net-(SENSORB-VCLAMP_ADC)") (class "Default")
      (node (ref "C60") (pin "1") (pinfunction "1_1") (pintype "passive"))
      (node (ref "SENSOR") (pin "G2") (pinfunction "VCLAMP_ADC_G2") (pintype "bidirectional"))
    )
    (net (code "121") (name "Net-(SENSORB-VPCH_H)") (class "Default")
      (node (ref "C71") (pin "1") (pinfunction "1_1") (pintype "passive"))
      (node (ref "SENSOR") (pin "C4") (pinfunction "VPCH_H_C4") (pintype "bidirectional"))
    )
    (net (code "122") (name "Net-(SENSORB-VPCH_L)") (class "Default")
      (node (ref "C14") (pin "1") (pinfunction "1_1") (pintype "passive"))
      (node (ref "SENSOR") (pin "A4") (pinfunction "VPCH_L_A4") (pintype "bidirectional"))
    )
    (net (code "123") (name "Net-(SENSORB-VREF)") (class "Default")
      (node (ref "C29") (pin "1") (pinfunction "1_1") (pintype "passive"))
      (node (ref "SENSOR") (pin "A3") (pinfunction "VREF_A3") (pintype "bidirectional"))
    )
    (net (code "124") (name "Net-(SENSORB-VREF_ADC)") (class "Default")
      (node (ref "C30") (pin "1") (pinfunction "1_1") (pintype "passive"))
      (node (ref "SENSOR") (pin "B3") (pinfunction "VREF_ADC_B3") (pintype "bidirectional"))
    )
    (net (code "125") (name "Net-(SENSORB-VRES_L)") (class "Default")
      (node (ref "C15") (pin "1") (pinfunction "1_1") (pintype "passive"))
      (node (ref "SENSOR") (pin "D5") (pinfunction "VRES_L_D5") (pintype "bidirectional"))
    )
    (net (code "126") (name "Net-(SENSORB-VTF_LOW0)") (class "Default")
      (node (ref "C18") (pin "1") (pinfunction "1_1") (pintype "passive"))
      (node (ref "SENSOR") (pin "C5") (pinfunction "VTF_LOW0_C5") (pintype "bidirectional"))
    )
    (net (code "127") (name "Net-(SENSORB-VTF_LOW1)") (class "Default")
      (node (ref "C19") (pin "1") (pinfunction "1_1") (pintype "passive"))
      (node (ref "SENSOR") (pin "D6") (pinfunction "VTF_LOW1_D6") (pintype "bidirectional"))
    )
    (net (code "128") (name "Net-(SENSORB-VTF_LOW2)") (class "Default")
      (node (ref "C20") (pin "1") (pinfunction "1_1") (pintype "passive"))
      (node (ref "SENSOR") (pin "B30") (pinfunction "VTF_LOW2_B30") (pintype "bidirectional"))
    )
    (net (code "129") (name "Net-(SENSORB-VTF_LOW3)") (class "Default")
      (node (ref "C21") (pin "1") (pinfunction "1_1") (pintype "passive"))
      (node (ref "SENSOR") (pin "C30") (pinfunction "VTF_LOW3_C30") (pintype "bidirectional"))
    )
    (net (code "130") (name "Net-(U3-ADJ)") (class "Default")
      (node (ref "R21") (pin "1") (pinfunction "1_1") (pintype "passive"))
      (node (ref "R22") (pin "2") (pinfunction "2_2") (pintype "passive"))
      (node (ref "U3") (pin "5") (pinfunction "ADJ_5") (pintype "input"))
    )
    (net (code "131") (name "Net-(U6-B4)") (class "Default")
      (node (ref "TP9") (pin "TP") (pinfunction "TP_TP") (pintype "input"))
      (node (ref "U6") (pin "9") (pinfunction "B4_9") (pintype "bidirectional"))
    )
    (net (code "132") (name "Net-(UEP-WP)") (class "Default")
      (node (ref "R1X") (pin "2") (pinfunction "2_2") (pintype "passive"))
      (node (ref "R2X") (pin "1") (pinfunction "1_1") (pintype "passive"))
      (node (ref "UEP") (pin "7") (pinfunction "WP_7") (pintype "input"))
    )
    (net (code "133") (name "Net-(UNE-VINA+)") (class "Default")
      (node (ref "R7") (pin "2") (pinfunction "2_2") (pintype "passive"))
      (node (ref "R8") (pin "1") (pinfunction "1_1") (pintype "passive"))
      (node (ref "UNE") (pin "3") (pinfunction "VINA+_3") (pintype "input"))
    )
    (net (code "134") (name "Net-(UNE-VINB-)") (class "Default")
      (node (ref "R8") (pin "2") (pinfunction "2_2") (pintype "passive"))
      (node (ref "R9") (pin "1") (pinfunction "1_1") (pintype "passive"))
      (node (ref "UNE") (pin "6") (pinfunction "VINB-_6") (pintype "input"))
    )
    (net (code "135") (name "Net-(UNN-VINA+)") (class "Default")
      (node (ref "R4") (pin "2") (pinfunction "2_2") (pintype "passive"))
      (node (ref "R5") (pin "1") (pinfunction "1_1") (pintype "passive"))
      (node (ref "UNN") (pin "3") (pinfunction "VINA+_3") (pintype "input"))
    )
    (net (code "136") (name "Net-(UNN-VINB-)") (class "Default")
      (node (ref "R5") (pin "2") (pinfunction "2_2") (pintype "passive"))
      (node (ref "R6") (pin "1") (pinfunction "1_1") (pintype "passive"))
      (node (ref "UNN") (pin "6") (pinfunction "VINB-_6") (pintype "input"))
    )
    (net (code "137") (name "Net-(UNW-VINA+)") (class "Default")
      (node (ref "R1") (pin "2") (pinfunction "2_2") (pintype "passive"))
      (node (ref "R2") (pin "1") (pinfunction "1_1") (pintype "passive"))
      (node (ref "UNW") (pin "3") (pinfunction "VINA+_3") (pintype "input"))
    )
    (net (code "138") (name "Net-(UNW-VINB-)") (class "Default")
      (node (ref "R2") (pin "2") (pinfunction "2_2") (pintype "passive"))
      (node (ref "R3") (pin "1") (pinfunction "1_1") (pintype "passive"))
      (node (ref "UNW") (pin "6") (pinfunction "VINB-_6") (pintype "input"))
    )
    (net (code "139") (name "Net-(USE-VINA+)") (class "Default")
      (node (ref "R10") (pin "2") (pinfunction "2_2") (pintype "passive"))
      (node (ref "R11") (pin "1") (pinfunction "1_1") (pintype "passive"))
      (node (ref "USE") (pin "3") (pinfunction "VINA+_3") (pintype "input"))
    )
    (net (code "140") (name "Net-(USE-VINB-)") (class "Default")
      (node (ref "R11") (pin "2") (pinfunction "2_2") (pintype "passive"))
      (node (ref "R12") (pin "1") (pinfunction "1_1") (pintype "passive"))
      (node (ref "USE") (pin "6") (pinfunction "VINB-_6") (pintype "input"))
    )
    (net (code "141") (name "Net-(USS-VINA+)") (class "Default")
      (node (ref "R13") (pin "2") (pinfunction "2_2") (pintype "passive"))
      (node (ref "R14") (pin "1") (pinfunction "1_1") (pintype "passive"))
      (node (ref "USS") (pin "3") (pinfunction "VINA+_3") (pintype "input"))
    )
    (net (code "142") (name "Net-(USS-VINB-)") (class "Default")
      (node (ref "R14") (pin "2") (pinfunction "2_2") (pintype "passive"))
      (node (ref "R15") (pin "1") (pinfunction "1_1") (pintype "passive"))
      (node (ref "USS") (pin "6") (pinfunction "VINB-_6") (pintype "input"))
    )
    (net (code "143") (name "Net-(USW-VINA+)") (class "Default")
      (node (ref "R16") (pin "2") (pinfunction "2_2") (pintype "passive"))
      (node (ref "R17") (pin "1") (pinfunction "1_1") (pintype "passive"))
      (node (ref "USW") (pin "3") (pinfunction "VINA+_3") (pintype "input"))
    )
    (net (code "144") (name "Net-(USW-VINB-)") (class "Default")
      (node (ref "R17") (pin "2") (pinfunction "2_2") (pintype "passive"))
      (node (ref "R18") (pin "1") (pinfunction "1_1") (pintype "passive"))
      (node (ref "USW") (pin "6") (pinfunction "VINB-_6") (pintype "input"))
    )
    (net (code "145") (name "S00_N") (class "Default")
      (node (ref "X-SOUTH") (pin "16") (pinfunction "16_16") (pintype "bidirectional"))
    )
    (net (code "146") (name "S00_P") (class "Default")
      (node (ref "X-SOUTH") (pin "14") (pinfunction "14_14") (pintype "bidirectional"))
    )
    (net (code "147") (name "S01_N") (class "Default")
      (node (ref "X-SOUTH") (pin "17") (pinfunction "17_17") (pintype "bidirectional"))
    )
    (net (code "148") (name "S01_P") (class "Default")
      (node (ref "X-SOUTH") (pin "15") (pinfunction "15_15") (pintype "bidirectional"))
    )
    (net (code "149") (name "S02_N") (class "Default")
      (node (ref "X-SOUTH") (pin "22") (pinfunction "22_22") (pintype "bidirectional"))
    )
    (net (code "150") (name "S02_P") (class "Default")
      (node (ref "X-SOUTH") (pin "20") (pinfunction "20_20") (pintype "bidirectional"))
    )
    (net (code "151") (name "S03_N") (class "Default")
      (node (ref "X-SOUTH") (pin "23") (pinfunction "23_23") (pintype "bidirectional"))
    )
    (net (code "152") (name "S03_P") (class "Default")
      (node (ref "X-SOUTH") (pin "21") (pinfunction "21_21") (pintype "bidirectional"))
    )
    (net (code "153") (name "S04_N") (class "Default")
      (node (ref "SENSOR") (pin "C24") (pinfunction "OUT32_N_C24") (pintype "output"))
      (node (ref "X-SOUTH") (pin "28") (pinfunction "28_28") (pintype "bidirectional"))
    )
    (net (code "154") (name "S04_P") (class "Default")
      (node (ref "SENSOR") (pin "C25") (pinfunction "OUT32_P_C25") (pintype "output"))
      (node (ref "X-SOUTH") (pin "26") (pinfunction "26_26") (pintype "bidirectional"))
    )
    (net (code "155") (name "S05_N") (class "Default")
      (node (ref "X-SOUTH") (pin "29") (pinfunction "29_29") (pintype "bidirectional"))
    )
    (net (code "156") (name "S05_P") (class "Default")
      (node (ref "X-SOUTH") (pin "27") (pinfunction "27_27") (pintype "bidirectional"))
    )
    (net (code "157") (name "S06_N") (class "Default")
      (node (ref "SENSOR") (pin "D23") (pinfunction "OUT30_N_D23") (pintype "output"))
      (node (ref "X-SOUTH") (pin "34") (pinfunction "34_34") (pintype "bidirectional"))
    )
    (net (code "158") (name "S06_P") (class "Default")
      (node (ref "SENSOR") (pin "D24") (pinfunction "OUT30_P_D24") (pintype "output"))
      (node (ref "X-SOUTH") (pin "32") (pinfunction "32_32") (pintype "bidirectional"))
    )
    (net (code "159") (name "S07_N") (class "Default")
      (node (ref "SENSOR") (pin "B24") (pinfunction "OUT31_N_B24") (pintype "output"))
      (node (ref "X-SOUTH") (pin "35") (pinfunction "35_35") (pintype "bidirectional"))
    )
    (net (code "160") (name "S07_P") (class "Default")
      (node (ref "SENSOR") (pin "B25") (pinfunction "OUT31_P_B25") (pintype "output"))
      (node (ref "X-SOUTH") (pin "33") (pinfunction "33_33") (pintype "bidirectional"))
    )
    (net (code "161") (name "S08_N") (class "Default")
      (node (ref "SENSOR") (pin "D21") (pinfunction "OUT27_N_D21") (pintype "output"))
      (node (ref "X-SOUTH") (pin "40") (pinfunction "40_40") (pintype "bidirectional"))
    )
    (net (code "162") (name "S08_P") (class "Default")
      (node (ref "SENSOR") (pin "D22") (pinfunction "OUT27_P_D22") (pintype "output"))
      (node (ref "X-SOUTH") (pin "38") (pinfunction "38_38") (pintype "bidirectional"))
    )
    (net (code "163") (name "S09_N") (class "Default")
      (node (ref "SENSOR") (pin "A23") (pinfunction "OUT29_N_A23") (pintype "output"))
      (node (ref "X-SOUTH") (pin "41") (pinfunction "41_41") (pintype "bidirectional"))
    )
    (net (code "164") (name "S09_P") (class "Default")
      (node (ref "SENSOR") (pin "A24") (pinfunction "OUT29_P_A24") (pintype "output"))
      (node (ref "X-SOUTH") (pin "39") (pinfunction "39_39") (pintype "bidirectional"))
    )
    (net (code "165") (name "S10_N") (class "Default")
      (node (ref "SENSOR") (pin "C21") (pinfunction "OUT28_N_C21") (pintype "output"))
      (node (ref "X-SOUTH") (pin "46") (pinfunction "46_46") (pintype "bidirectional"))
    )
    (net (code "166") (name "S10_P") (class "Default")
      (node (ref "SENSOR") (pin "C22") (pinfunction "OUT28_P_C22") (pintype "output"))
      (node (ref "X-SOUTH") (pin "44") (pinfunction "44_44") (pintype "bidirectional"))
    )
    (net (code "167") (name "S11_N") (class "Default")
      (node (ref "SENSOR") (pin "B20") (pinfunction "OUT26_N_B20") (pintype "output"))
      (node (ref "X-SOUTH") (pin "47") (pinfunction "47_47") (pintype "bidirectional"))
    )
    (net (code "168") (name "S11_P") (class "Default")
      (node (ref "SENSOR") (pin "B21") (pinfunction "OUT26_P_B21") (pintype "output"))
      (node (ref "X-SOUTH") (pin "45") (pinfunction "45_45") (pintype "bidirectional"))
    )
    (net (code "169") (name "S12_N") (class "Default")
      (node (ref "SENSOR") (pin "D19") (pinfunction "OUT24_N_D19") (pintype "output"))
      (node (ref "X-SOUTH") (pin "52") (pinfunction "52_52") (pintype "bidirectional"))
    )
    (net (code "170") (name "S12_P") (class "Default")
      (node (ref "SENSOR") (pin "D20") (pinfunction "OUT24_P_D20") (pintype "output"))
      (node (ref "X-SOUTH") (pin "50") (pinfunction "50_50") (pintype "bidirectional"))
    )
    (net (code "171") (name "S13_N") (class "Default")
      (node (ref "SENSOR") (pin "A19") (pinfunction "OUT23_N_A19") (pintype "output"))
      (node (ref "X-SOUTH") (pin "53") (pinfunction "53_53") (pintype "bidirectional"))
    )
    (net (code "172") (name "S13_P") (class "Default")
      (node (ref "SENSOR") (pin "A20") (pinfunction "OUT23_P_A20") (pintype "output"))
      (node (ref "X-SOUTH") (pin "51") (pinfunction "51_51") (pintype "bidirectional"))
    )
    (net (code "173") (name "S14_N") (class "Default")
      (node (ref "SENSOR") (pin "C19") (pinfunction "OUT25_N_C19") (pintype "output"))
      (node (ref "X-SOUTH") (pin "58") (pinfunction "58_58") (pintype "bidirectional"))
    )
    (net (code "174") (name "S14_P") (class "Default")
      (node (ref "SENSOR") (pin "C20") (pinfunction "OUT25_P_C20") (pintype "output"))
      (node (ref "X-SOUTH") (pin "56") (pinfunction "56_56") (pintype "bidirectional"))
    )
    (net (code "175") (name "S15_N") (class "Default")
      (node (ref "SENSOR") (pin "B18") (pinfunction "OUT22_N_B18") (pintype "output"))
      (node (ref "X-SOUTH") (pin "59") (pinfunction "59_59") (pintype "bidirectional"))
    )
    (net (code "176") (name "S15_P") (class "Default")
      (node (ref "SENSOR") (pin "B19") (pinfunction "OUT22_P_B19") (pintype "output"))
      (node (ref "X-SOUTH") (pin "57") (pinfunction "57_57") (pintype "bidirectional"))
    )
    (net (code "177") (name "S16_N") (class "Default")
      (node (ref "SENSOR") (pin "C17") (pinfunction "OUT21_N_C17") (pintype "output"))
      (node (ref "X-SOUTH") (pin "64") (pinfunction "64_64") (pintype "bidirectional"))
    )
    (net (code "178") (name "S16_P") (class "Default")
      (node (ref "SENSOR") (pin "C18") (pinfunction "OUT21_P_C18") (pintype "output"))
      (node (ref "X-SOUTH") (pin "62") (pinfunction "62_62") (pintype "bidirectional"))
    )
    (net (code "179") (name "S17_N") (class "Default")
      (node (ref "SENSOR") (pin "A17") (pinfunction "OUT19_N_A17") (pintype "output"))
      (node (ref "X-SOUTH") (pin "65") (pinfunction "65_65") (pintype "bidirectional"))
    )
    (net (code "180") (name "S17_P") (class "Default")
      (node (ref "SENSOR") (pin "A18") (pinfunction "OUT19_P_A18") (pintype "output"))
      (node (ref "X-SOUTH") (pin "63") (pinfunction "63_63") (pintype "bidirectional"))
    )
    (net (code "181") (name "S18_N") (class "Default")
      (node (ref "SENSOR") (pin "D17") (pinfunction "OUT20_N_D17") (pintype "output"))
      (node (ref "X-SOUTH") (pin "70") (pinfunction "70_70") (pintype "bidirectional"))
    )
    (net (code "182") (name "S18_P") (class "Default")
      (node (ref "SENSOR") (pin "D18") (pinfunction "OUT20_P_D18") (pintype "output"))
      (node (ref "X-SOUTH") (pin "68") (pinfunction "68_68") (pintype "bidirectional"))
    )
    (net (code "183") (name "S19_N") (class "Default")
      (node (ref "SENSOR") (pin "B16") (pinfunction "OUT18_N_B16") (pintype "output"))
      (node (ref "X-SOUTH") (pin "71") (pinfunction "71_71") (pintype "bidirectional"))
    )
    (net (code "184") (name "S19_P") (class "Default")
      (node (ref "SENSOR") (pin "B17") (pinfunction "OUT18_P_B17") (pintype "output"))
      (node (ref "X-SOUTH") (pin "69") (pinfunction "69_69") (pintype "bidirectional"))
    )
    (net (code "185") (name "S20_N") (class "Default")
      (node (ref "SENSOR") (pin "D15") (pinfunction "OUT17_N_D15") (pintype "output"))
      (node (ref "X-SOUTH") (pin "76") (pinfunction "76_76") (pintype "bidirectional"))
    )
    (net (code "186") (name "S20_P") (class "Default")
      (node (ref "SENSOR") (pin "D16") (pinfunction "OUT17_P_D16") (pintype "output"))
      (node (ref "X-SOUTH") (pin "74") (pinfunction "74_74") (pintype "bidirectional"))
    )
    (net (code "187") (name "S21_N") (class "Default")
      (node (ref "SENSOR") (pin "B14") (pinfunction "OUT16_N_B14") (pintype "output"))
      (node (ref "X-SOUTH") (pin "77") (pinfunction "77_77") (pintype "bidirectional"))
    )
    (net (code "188") (name "S21_P") (class "Default")
      (node (ref "SENSOR") (pin "B15") (pinfunction "OUT16_P_B15") (pintype "output"))
      (node (ref "X-SOUTH") (pin "75") (pinfunction "75_75") (pintype "bidirectional"))
    )
    (net (code "189") (name "S22_N") (class "Default")
      (node (ref "SENSOR") (pin "D13") (pinfunction "OUT15_N_D13") (pintype "output"))
      (node (ref "X-SOUTH") (pin "82") (pinfunction "82_82") (pintype "bidirectional"))
    )
    (net (code "190") (name "S22_P") (class "Default")
      (node (ref "SENSOR") (pin "D14") (pinfunction "OUT15_P_D14") (pintype "output"))
      (node (ref "X-SOUTH") (pin "80") (pinfunction "80_80") (pintype "bidirectional"))
    )
    (net (code "191") (name "S23_N") (class "Default")
      (node (ref "SENSOR") (pin "A13") (pinfunction "OUT13_N_A13") (pintype "output"))
      (node (ref "X-SOUTH") (pin "83") (pinfunction "83_83") (pintype "bidirectional"))
    )
    (net (code "192") (name "S23_P") (class "Default")
      (node (ref "SENSOR") (pin "A14") (pinfunction "OUT13_P_A14") (pintype "output"))
      (node (ref "X-SOUTH") (pin "81") (pinfunction "81_81") (pintype "bidirectional"))
    )
    (net (code "193") (name "S24_N") (class "Default")
      (node (ref "SENSOR") (pin "C13") (pinfunction "OUT14_N_C13") (pintype "output"))
      (node (ref "X-SOUTH") (pin "88") (pinfunction "88_88") (pintype "bidirectional"))
    )
    (net (code "194") (name "S24_P") (class "Default")
      (node (ref "SENSOR") (pin "C14") (pinfunction "OUT14_P_C14") (pintype "output"))
      (node (ref "X-SOUTH") (pin "86") (pinfunction "86_86") (pintype "bidirectional"))
    )
    (net (code "195") (name "S25_N") (class "Default")
      (node (ref "SENSOR") (pin "B12") (pinfunction "OUT12_N_B12") (pintype "output"))
      (node (ref "X-SOUTH") (pin "89") (pinfunction "89_89") (pintype "bidirectional"))
    )
    (net (code "196") (name "S25_P") (class "Default")
      (node (ref "SENSOR") (pin "B13") (pinfunction "OUT12_P_B13") (pintype "output"))
      (node (ref "X-SOUTH") (pin "87") (pinfunction "87_87") (pintype "bidirectional"))
    )
    (net (code "197") (name "S26_N") (class "Default")
      (node (ref "SENSOR") (pin "D11") (pinfunction "OUT10_N_D11") (pintype "output"))
      (node (ref "X-SOUTH") (pin "94") (pinfunction "94_94") (pintype "bidirectional"))
    )
    (net (code "198") (name "S26_P") (class "Default")
      (node (ref "SENSOR") (pin "D12") (pinfunction "OUT10_P_D12") (pintype "output"))
      (node (ref "X-SOUTH") (pin "92") (pinfunction "92_92") (pintype "bidirectional"))
    )
    (net (code "199") (name "S27_N") (class "Default")
      (node (ref "SENSOR") (pin "A11") (pinfunction "OUT9_N_A11") (pintype "output"))
      (node (ref "X-SOUTH") (pin "95") (pinfunction "95_95") (pintype "bidirectional"))
    )
    (net (code "200") (name "S27_P") (class "Default")
      (node (ref "SENSOR") (pin "A12") (pinfunction "OUT9_P_A12") (pintype "output"))
      (node (ref "X-SOUTH") (pin "93") (pinfunction "93_93") (pintype "bidirectional"))
    )
    (net (code "201") (name "S28_N") (class "Default")
      (node (ref "SENSOR") (pin "C11") (pinfunction "OUT11_N_C11") (pintype "output"))
      (node (ref "X-SOUTH") (pin "100") (pinfunction "100_100") (pintype "bidirectional"))
    )
    (net (code "202") (name "S28_P") (class "Default")
      (node (ref "SENSOR") (pin "C12") (pinfunction "OUT11_P_C12") (pintype "output"))
      (node (ref "X-SOUTH") (pin "98") (pinfunction "98_98") (pintype "bidirectional"))
    )
    (net (code "203") (name "S29_N") (class "Default")
      (node (ref "SENSOR") (pin "B10") (pinfunction "OUT8_N_B10") (pintype "output"))
      (node (ref "X-SOUTH") (pin "101") (pinfunction "101_101") (pintype "bidirectional"))
    )
    (net (code "204") (name "S29_P") (class "Default")
      (node (ref "SENSOR") (pin "B11") (pinfunction "OUT8_P_B11") (pintype "output"))
      (node (ref "X-SOUTH") (pin "99") (pinfunction "99_99") (pintype "bidirectional"))
    )
    (net (code "205") (name "S30_N") (class "Default")
      (node (ref "SENSOR") (pin "C9") (pinfunction "OUT7_N_C9") (pintype "output"))
      (node (ref "X-SOUTH") (pin "106") (pinfunction "106_106") (pintype "bidirectional"))
    )
    (net (code "206") (name "S30_P") (class "Default")
      (node (ref "SENSOR") (pin "C10") (pinfunction "OUT7_P_C10") (pintype "output"))
      (node (ref "X-SOUTH") (pin "104") (pinfunction "104_104") (pintype "bidirectional"))
    )
    (net (code "207") (name "S31_N") (class "Default")
      (node (ref "SENSOR") (pin "B8") (pinfunction "OUT5_N_B8") (pintype "output"))
      (node (ref "X-SOUTH") (pin "107") (pinfunction "107_107") (pintype "bidirectional"))
    )
    (net (code "208") (name "S31_P") (class "Default")
      (node (ref "SENSOR") (pin "B9") (pinfunction "OUT5_P_B9") (pintype "output"))
      (node (ref "X-SOUTH") (pin "105") (pinfunction "105_105") (pintype "bidirectional"))
    )
    (net (code "209") (name "S32_N") (class "Default")
      (node (ref "SENSOR") (pin "D9") (pinfunction "OUT6_N_D9") (pintype "output"))
      (node (ref "X-SOUTH") (pin "112") (pinfunction "112_112") (pintype "bidirectional"))
    )
    (net (code "210") (name "S32_P") (class "Default")
      (node (ref "SENSOR") (pin "D10") (pinfunction "OUT6_P_D10") (pintype "output"))
      (node (ref "X-SOUTH") (pin "110") (pinfunction "110_110") (pintype "bidirectional"))
    )
    (net (code "211") (name "S33_N") (class "Default")
      (node (ref "SENSOR") (pin "A7") (pinfunction "OUT2_N_A7") (pintype "output"))
      (node (ref "X-SOUTH") (pin "113") (pinfunction "113_113") (pintype "bidirectional"))
    )
    (net (code "212") (name "S33_P") (class "Default")
      (node (ref "SENSOR") (pin "A8") (pinfunction "OUT2_P_A8") (pintype "output"))
      (node (ref "X-SOUTH") (pin "111") (pinfunction "111_111") (pintype "bidirectional"))
    )
    (net (code "213") (name "S34_N") (class "Default")
      (node (ref "SENSOR") (pin "C7") (pinfunction "OUT4_N_C7") (pintype "output"))
      (node (ref "X-SOUTH") (pin "118") (pinfunction "118_118") (pintype "bidirectional"))
    )
    (net (code "214") (name "S34_P") (class "Default")
      (node (ref "SENSOR") (pin "C8") (pinfunction "OUT4_P_C8") (pintype "output"))
      (node (ref "X-SOUTH") (pin "116") (pinfunction "116_116") (pintype "bidirectional"))
    )
    (net (code "215") (name "S35_N") (class "Default")
      (node (ref "SENSOR") (pin "B6") (pinfunction "OUT1_N_B6") (pintype "output"))
      (node (ref "X-SOUTH") (pin "119") (pinfunction "119_119") (pintype "bidirectional"))
    )
    (net (code "216") (name "S35_P") (class "Default")
      (node (ref "SENSOR") (pin "B7") (pinfunction "OUT1_P_B7") (pintype "output"))
      (node (ref "X-SOUTH") (pin "117") (pinfunction "117_117") (pintype "bidirectional"))
    )
    (net (code "217") (name "S36_N") (class "Default")
      (node (ref "SENSOR") (pin "D7") (pinfunction "OUT3_N_D7") (pintype "output"))
      (node (ref "X-SOUTH") (pin "124") (pinfunction "124_124") (pintype "bidirectional"))
    )
    (net (code "218") (name "S36_P") (class "Default")
      (node (ref "SENSOR") (pin "D8") (pinfunction "OUT3_P_D8") (pintype "output"))
      (node (ref "X-SOUTH") (pin "122") (pinfunction "122_122") (pintype "bidirectional"))
    )
    (net (code "219") (name "S37_N") (class "Default")
      (node (ref "SENSOR") (pin "A5") (pinfunction "OUTCTR_N_A5") (pintype "output"))
      (node (ref "X-SOUTH") (pin "125") (pinfunction "125_125") (pintype "bidirectional"))
    )
    (net (code "220") (name "S37_P") (class "Default")
      (node (ref "SENSOR") (pin "A6") (pinfunction "OUTCTR_P_A6") (pintype "output"))
      (node (ref "X-SOUTH") (pin "123") (pinfunction "123_123") (pintype "bidirectional"))
    )
    (net (code "221") (name "S38_N") (class "Default")
      (node (ref "X-SOUTH") (pin "130") (pinfunction "130_130") (pintype "bidirectional"))
    )
    (net (code "222") (name "S38_P") (class "Default")
      (node (ref "X-SOUTH") (pin "128") (pinfunction "128_128") (pintype "bidirectional"))
    )
    (net (code "223") (name "S39_N") (class "Default")
      (node (ref "U3") (pin "6") (pinfunction "EN_6") (pintype "input"))
      (node (ref "X-SOUTH") (pin "131") (pinfunction "131_131") (pintype "bidirectional"))
    )
    (net (code "224") (name "S39_P") (class "Default")
      (node (ref "X-SOUTH") (pin "129") (pinfunction "129_129") (pintype "bidirectional"))
    )
    (net (code "225") (name "SPI_CLK") (class "Default")
      (node (ref "SENSOR") (pin "H29") (pinfunction "SPI_CLK_H29") (pintype "input"))
      (node (ref "U4") (pin "9") (pinfunction "B4_9") (pintype "bidirectional"))
    )
    (net (code "226") (name "SPI_EN") (class "Default")
      (node (ref "SENSOR") (pin "F28") (pinfunction "SPI_EN_F28") (pintype "input"))
      (node (ref "U4") (pin "12") (pinfunction "B1_12") (pintype "bidirectional"))
    )
    (net (code "227") (name "SPI_IN") (class "Default")
      (node (ref "SENSOR") (pin "E28") (pinfunction "SPI_IN_E28") (pintype "input"))
      (node (ref "U4") (pin "10") (pinfunction "B3_10") (pintype "bidirectional"))
    )
    (net (code "228") (name "SPI_OUT") (class "Default")
      (node (ref "SENSOR") (pin "G28") (pinfunction "SPI_OUT_G28") (pintype "output"))
      (node (ref "U4") (pin "11") (pinfunction "B2_11") (pintype "bidirectional"))
    )
    (net (code "229") (name "SYS_RES_N") (class "Default")
      (node (ref "SENSOR") (pin "F30") (pinfunction "SYS_RES_N_F30") (pintype "input"))
      (node (ref "U5") (pin "10") (pinfunction "B3_10") (pintype "bidirectional"))
    )
    (net (code "230") (name "S_CHK_EN") (class "Default")
      (node (ref "X-SOUTH") (pin "8") (pinfunction "8_8") (pintype "bidirectional"))
    )
    (net (code "231") (name "S_CHK_V") (class "Default")
      (node (ref "C5") (pin "1") (pinfunction "1_1") (pintype "passive"))
      (node (ref "C6") (pin "1") (pinfunction "1_1") (pintype "passive"))
      (node (ref "C7") (pin "1") (pinfunction "1_1") (pintype "passive"))
      (node (ref "R20") (pin "1") (pinfunction "1_1") (pintype "passive"))
      (node (ref "TP3") (pin "TP") (pinfunction "TP_TP") (pintype "input"))
      (node (ref "USE") (pin "8") (pinfunction "VDD_8") (pintype "power_in"))
      (node (ref "USS") (pin "8") (pinfunction "VDD_8") (pintype "power_in"))
      (node (ref "USW") (pin "8") (pinfunction "VDD_8") (pintype "power_in"))
      (node (ref "X-SOUTH") (pin "10") (pinfunction "10_10") (pintype "bidirectional"))
    )
    (net (code "232") (name "S_I2C_EN") (class "Default")
      (node (ref "X-SOUTH") (pin "137") (pinfunction "137_137") (pintype "bidirectional"))
    )
    (net (code "233") (name "S_I2C_V") (class "Default")
      (node (ref "U7") (pin "8") (pinfunction "VCC_8") (pintype "power_in"))
      (node (ref "X-SOUTH") (pin "135") (pinfunction "135_135") (pintype "bidirectional"))
    )
    (net (code "234") (name "S_REF") (class "Default")
      (node (ref "R20") (pin "2") (pinfunction "2_2") (pintype "passive"))
      (node (ref "TP4") (pin "TP") (pinfunction "TP_TP") (pintype "input"))
      (node (ref "U2") (pin "1") (pinfunction "CATHODE_1") (pintype "output"))
      (node (ref "U2") (pin "3") (pinfunction "REF_3") (pintype "input"))
      (node (ref "USE") (pin "2") (pinfunction "VINA-_2") (pintype "input"))
      (node (ref "USE") (pin "5") (pinfunction "VINB+_5") (pintype "input"))
      (node (ref "USS") (pin "2") (pinfunction "VINA-_2") (pintype "input"))
      (node (ref "USS") (pin "5") (pinfunction "VINB+_5") (pintype "input"))
      (node (ref "USW") (pin "2") (pinfunction "VINA-_2") (pintype "input"))
      (node (ref "USW") (pin "5") (pinfunction "VINB+_5") (pintype "input"))
    )
    (net (code "235") (name "S_SCK") (class "Default")
      (node (ref "X-SOUTH") (pin "144") (pinfunction "144_144") (pintype "bidirectional"))
    )
    (net (code "236") (name "S_SCL") (class "Default")
      (node (ref "U7") (pin "2") (pinfunction "SCL_2") (pintype "input"))
      (node (ref "X-SOUTH") (pin "143") (pinfunction "143_143") (pintype "bidirectional"))
    )
    (net (code "237") (name "S_SDA") (class "Default")
      (node (ref "U7") (pin "1") (pinfunction "SDA_1") (pintype "bidirectional"))
      (node (ref "X-SOUTH") (pin "141") (pinfunction "141_141") (pintype "bidirectional"))
    )
    (net (code "238") (name "S_SDI") (class "Default")
      (node (ref "X-SOUTH") (pin "140") (pinfunction "140_140") (pintype "bidirectional"))
    )
    (net (code "239") (name "S_SDO") (class "Default")
      (node (ref "X-SOUTH") (pin "142") (pinfunction "142_142") (pintype "bidirectional"))
    )
    (net (code "240") (name "S_SPI_EN") (class "Default")
      (node (ref "X-SOUTH") (pin "136") (pinfunction "136_136") (pintype "bidirectional"))
    )
    (net (code "241") (name "S_SPI_V") (class "Default")
      (node (ref "X-SOUTH") (pin "134") (pinfunction "134_134") (pintype "bidirectional"))
    )
    (net (code "242") (name "S_VE") (class "Default")
      (node (ref "X-SOUTH") (pin "13") (pinfunction "13_13") (pintype "bidirectional"))
      (node (ref "X-SOUTH") (pin "19") (pinfunction "19_19") (pintype "bidirectional"))
      (node (ref "X-SOUTH") (pin "25") (pinfunction "25_25") (pintype "bidirectional"))
      (node (ref "X-SOUTH") (pin "31") (pinfunction "31_31") (pintype "bidirectional"))
      (node (ref "X-SOUTH") (pin "37") (pinfunction "37_37") (pintype "bidirectional"))
    )
    (net (code "243") (name "S_VE_CV") (class "Default")
      (node (ref "C11") (pin "1") (pinfunction "1_1") (pintype "passive"))
      (node (ref "R10") (pin "1") (pinfunction "1_1") (pintype "passive"))
      (node (ref "X-SOUTH") (pin "2") (pinfunction "2_2") (pintype "bidirectional"))
    )
    (net (code "244") (name "S_VE_OV") (class "Default")
      (node (ref "USE") (pin "7") (pinfunction "OUTB_7") (pintype "output"))
      (node (ref "X-SOUTH") (pin "1") (pinfunction "1_1") (pintype "bidirectional"))
    )
    (net (code "245") (name "S_VE_UV") (class "Default")
      (node (ref "USE") (pin "1") (pinfunction "OUTA_1") (pintype "output"))
      (node (ref "X-SOUTH") (pin "7") (pinfunction "7_7") (pintype "bidirectional"))
    )
    (net (code "246") (name "S_VS") (class "Default")
      (node (ref "C45") (pin "1") (pinfunction "1_1") (pintype "passive"))
      (node (ref "C46") (pin "1") (pinfunction "1_1") (pintype "passive"))
      (node (ref "C47") (pin "1") (pinfunction "1_1") (pintype "passive"))
      (node (ref "C48") (pin "1") (pinfunction "1_1") (pintype "passive"))
      (node (ref "C49") (pin "1") (pinfunction "1_1") (pintype "passive"))
      (node (ref "C72") (pin "1") (pinfunction "1_1") (pintype "passive"))
      (node (ref "C73") (pin "1") (pinfunction "1_1") (pintype "passive"))
      (node (ref "C74") (pin "1") (pinfunction "1_1") (pintype "passive"))
      (node (ref "C81") (pin "1") (pinfunction "1_1") (pintype "passive"))
      (node (ref "C82") (pin "1") (pinfunction "1_1") (pintype "passive"))
      (node (ref "C83") (pin "1") (pinfunction "1_1") (pintype "passive"))
      (node (ref "SENSOR") (pin "A30") (pinfunction "VDD_PIX_A30") (pintype "power_in"))
      (node (ref "SENSOR") (pin "D28") (pinfunction "VDD_PIX_D28") (pintype "power_in"))
      (node (ref "SENSOR") (pin "D30") (pinfunction "VDD_PIX_D30") (pintype "power_in"))
      (node (ref "SENSOR") (pin "G1") (pinfunction "VDD_PIX_G1") (pintype "power_in"))
      (node (ref "SENSOR") (pin "H28") (pinfunction "VDD_PIX_H28") (pintype "power_in"))
      (node (ref "TP6") (pin "TP") (pinfunction "TP_TP") (pintype "input"))
      (node (ref "X-SOUTH") (pin "49") (pinfunction "49_49") (pintype "bidirectional"))
      (node (ref "X-SOUTH") (pin "55") (pinfunction "55_55") (pintype "bidirectional"))
      (node (ref "X-SOUTH") (pin "61") (pinfunction "61_61") (pintype "bidirectional"))
      (node (ref "X-SOUTH") (pin "67") (pinfunction "67_67") (pintype "bidirectional"))
      (node (ref "X-SOUTH") (pin "73") (pinfunction "73_73") (pintype "bidirectional"))
      (node (ref "X-SOUTH") (pin "79") (pinfunction "79_79") (pintype "bidirectional"))
      (node (ref "X-SOUTH") (pin "85") (pinfunction "85_85") (pintype "bidirectional"))
      (node (ref "X-SOUTH") (pin "91") (pinfunction "91_91") (pintype "bidirectional"))
      (node (ref "X-SOUTH") (pin "97") (pinfunction "97_97") (pintype "bidirectional"))
    )
    (net (code "247") (name "S_VS_CV") (class "Default")
      (node (ref "C12") (pin "1") (pinfunction "1_1") (pintype "passive"))
      (node (ref "R13") (pin "1") (pinfunction "1_1") (pintype "passive"))
      (node (ref "X-SOUTH") (pin "4") (pinfunction "4_4") (pintype "bidirectional"))
    )
    (net (code "248") (name "S_VS_OV") (class "Default")
      (node (ref "USS") (pin "7") (pinfunction "OUTB_7") (pintype "output"))
      (node (ref "X-SOUTH") (pin "3") (pinfunction "3_3") (pintype "bidirectional"))
    )
    (net (code "249") (name "S_VS_UV") (class "Default")
      (node (ref "USS") (pin "1") (pinfunction "OUTA_1") (pintype "output"))
      (node (ref "X-SOUTH") (pin "9") (pinfunction "9_9") (pintype "bidirectional"))
    )
    (net (code "250") (name "S_VW") (class "Default")
      (node (ref "C90") (pin "1") (pinfunction "1_1") (pintype "passive"))
      (node (ref "U3") (pin "1") (pinfunction "BIAS_1") (pintype "power_in"))
      (node (ref "U3") (pin "3") (pinfunction "IN_3") (pintype "power_in"))
      (node (ref "X-SOUTH") (pin "109") (pinfunction "109_109") (pintype "bidirectional"))
      (node (ref "X-SOUTH") (pin "115") (pinfunction "115_115") (pintype "bidirectional"))
      (node (ref "X-SOUTH") (pin "121") (pinfunction "121_121") (pintype "bidirectional"))
      (node (ref "X-SOUTH") (pin "127") (pinfunction "127_127") (pintype "bidirectional"))
      (node (ref "X-SOUTH") (pin "133") (pinfunction "133_133") (pintype "bidirectional"))
    )
    (net (code "251") (name "S_VW_CV") (class "Default")
      (node (ref "C13") (pin "1") (pinfunction "1_1") (pintype "passive"))
      (node (ref "R16") (pin "1") (pinfunction "1_1") (pintype "passive"))
      (node (ref "X-SOUTH") (pin "6") (pinfunction "6_6") (pintype "bidirectional"))
    )
    (net (code "252") (name "S_VW_OV") (class "Default")
      (node (ref "USW") (pin "7") (pinfunction "OUTB_7") (pintype "output"))
      (node (ref "X-SOUTH") (pin "5") (pinfunction "5_5") (pintype "bidirectional"))
    )
    (net (code "253") (name "S_VW_UV") (class "Default")
      (node (ref "USW") (pin "1") (pinfunction "OUTA_1") (pintype "output"))
      (node (ref "X-SOUTH") (pin "11") (pinfunction "11_11") (pintype "bidirectional"))
    )
    (net (code "254") (name "TDIG1") (class "Default")
      (node (ref "SENSOR") (pin "G27") (pinfunction "TDIG1_G27") (pintype "output"))
      (node (ref "U5") (pin "9") (pinfunction "B4_9") (pintype "bidirectional"))
    )
    (net (code "255") (name "TDIG2") (class "Default")
      (node (ref "SENSOR") (pin "G26") (pinfunction "TDIG2_G26") (pintype "output"))
      (node (ref "U6") (pin "11") (pinfunction "B2_11") (pintype "bidirectional"))
    )
    (net (code "256") (name "T_EXP1") (class "Default")
      (node (ref "SENSOR") (pin "H30") (pinfunction "T_EXP1_H30") (pintype "input"))
      (node (ref "U5") (pin "12") (pinfunction "B1_12") (pintype "bidirectional"))
    )
    (net (code "257") (name "T_EXP2") (class "Default")
      (node (ref "SENSOR") (pin "E29") (pinfunction "T_EXP2_E29") (pintype "input"))
      (node (ref "U6") (pin "10") (pinfunction "B3_10") (pintype "bidirectional"))
    )
    (net (code "258") (name "VRAMP1") (class "Default")
      (node (ref "C16") (pin "1") (pinfunction "1_1") (pintype "passive"))
      (node (ref "R23") (pin "1") (pinfunction "1_1") (pintype "passive"))
      (node (ref "SENSOR") (pin "G29") (pinfunction "VRAMP1_G29") (pintype "bidirectional"))
    )
    (net (code "259") (name "VRAMP2") (class "Default")
      (node (ref "C17") (pin "1") (pinfunction "1_1") (pintype "passive"))
      (node (ref "R23") (pin "2") (pinfunction "2_2") (pintype "passive"))
      (node (ref "SENSOR") (pin "F29") (pinfunction "VRAMP2_F29") (pintype "bidirectional"))
    )
    (net (code "260") (name "VTREF") (class "Default")
      (node (ref "C65") (pin "1") (pinfunction "1_1") (pintype "passive"))
      (node (ref "C91") (pin "2") (pinfunction "2_2") (pintype "passive"))
      (node (ref "R21") (pin "2") (pinfunction "2_2") (pintype "passive"))
      (node (ref "R24") (pin "1") (pinfunction "1_1") (pintype "passive"))
      (node (ref "SENSOR") (pin "B2") (pinfunction "VTREF_B2") (pintype "bidirectional"))
      (node (ref "U3") (pin "4") (pinfunction "OUT_4") (pintype "power_in"))
    )
    (net (code "261") (name "VTSIG") (class "Default")
      (node (ref "C66") (pin "1") (pinfunction "1_1") (pintype "passive"))
      (node (ref "R24") (pin "2") (pinfunction "2_2") (pintype "passive"))
      (node (ref "SENSOR") (pin "C2") (pinfunction "VTSIG_C2") (pintype "bidirectional"))
    )
    (net (code "262") (name "unconnected-(U1-NC-Pad2)") (class "Default")
      (node (ref "U1") (pin "2") (pinfunction "NC_2") (pintype "no_connect"))
    )
    (net (code "263") (name "unconnected-(U1-NC-Pad4)") (class "Default")
      (node (ref "U1") (pin "4") (pinfunction "NC_4") (pintype "no_connect"))
    )
    (net (code "264") (name "unconnected-(U1-NC-Pad5)") (class "Default")
      (node (ref "U1") (pin "5") (pinfunction "NC_5") (pintype "no_connect"))
    )
    (net (code "265") (name "unconnected-(U2-NC-Pad2)") (class "Default")
      (node (ref "U2") (pin "2") (pinfunction "NC_2") (pintype "no_connect"))
    )
    (net (code "266") (name "unconnected-(U2-NC-Pad4)") (class "Default")
      (node (ref "U2") (pin "4") (pinfunction "NC_4") (pintype "no_connect"))
    )
    (net (code "267") (name "unconnected-(U2-NC-Pad5)") (class "Default")
      (node (ref "U2") (pin "5") (pinfunction "NC_5") (pintype "no_connect"))
    )
    (net (code "268") (name "unconnected-(U7-OS-Pad3)") (class "Default")
      (node (ref "U7") (pin "3") (pinfunction "OS_3") (pintype "output"))
    )
    (net (code "269") (name "unconnected-(X-NORTH-PadM1)") (class "Default")
      (node (ref "X-NORTH") (pin "M1") (pinfunction "M1_M1") (pintype "bidirectional"))
    )
    (net (code "270") (name "unconnected-(X-NORTH-PadM2)") (class "Default")
      (node (ref "X-NORTH") (pin "M2") (pinfunction "M2_M2") (pintype "bidirectional"))
    )
    (net (code "271") (name "unconnected-(X-SOUTH-PadM1)") (class "Default")
      (node (ref "X-SOUTH") (pin "M1") (pinfunction "M1_M1") (pintype "bidirectional"))
    )
    (net (code "272") (name "unconnected-(X-SOUTH-PadM2)") (class "Default")
      (node (ref "X-SOUTH") (pin "M2") (pinfunction "M2_M2") (pintype "bidirectional"))
    )
  )
)
